# AT32M412_EVB_V0_4.net
KiCad netlist of a schematic drawn in EasyEDA Pro
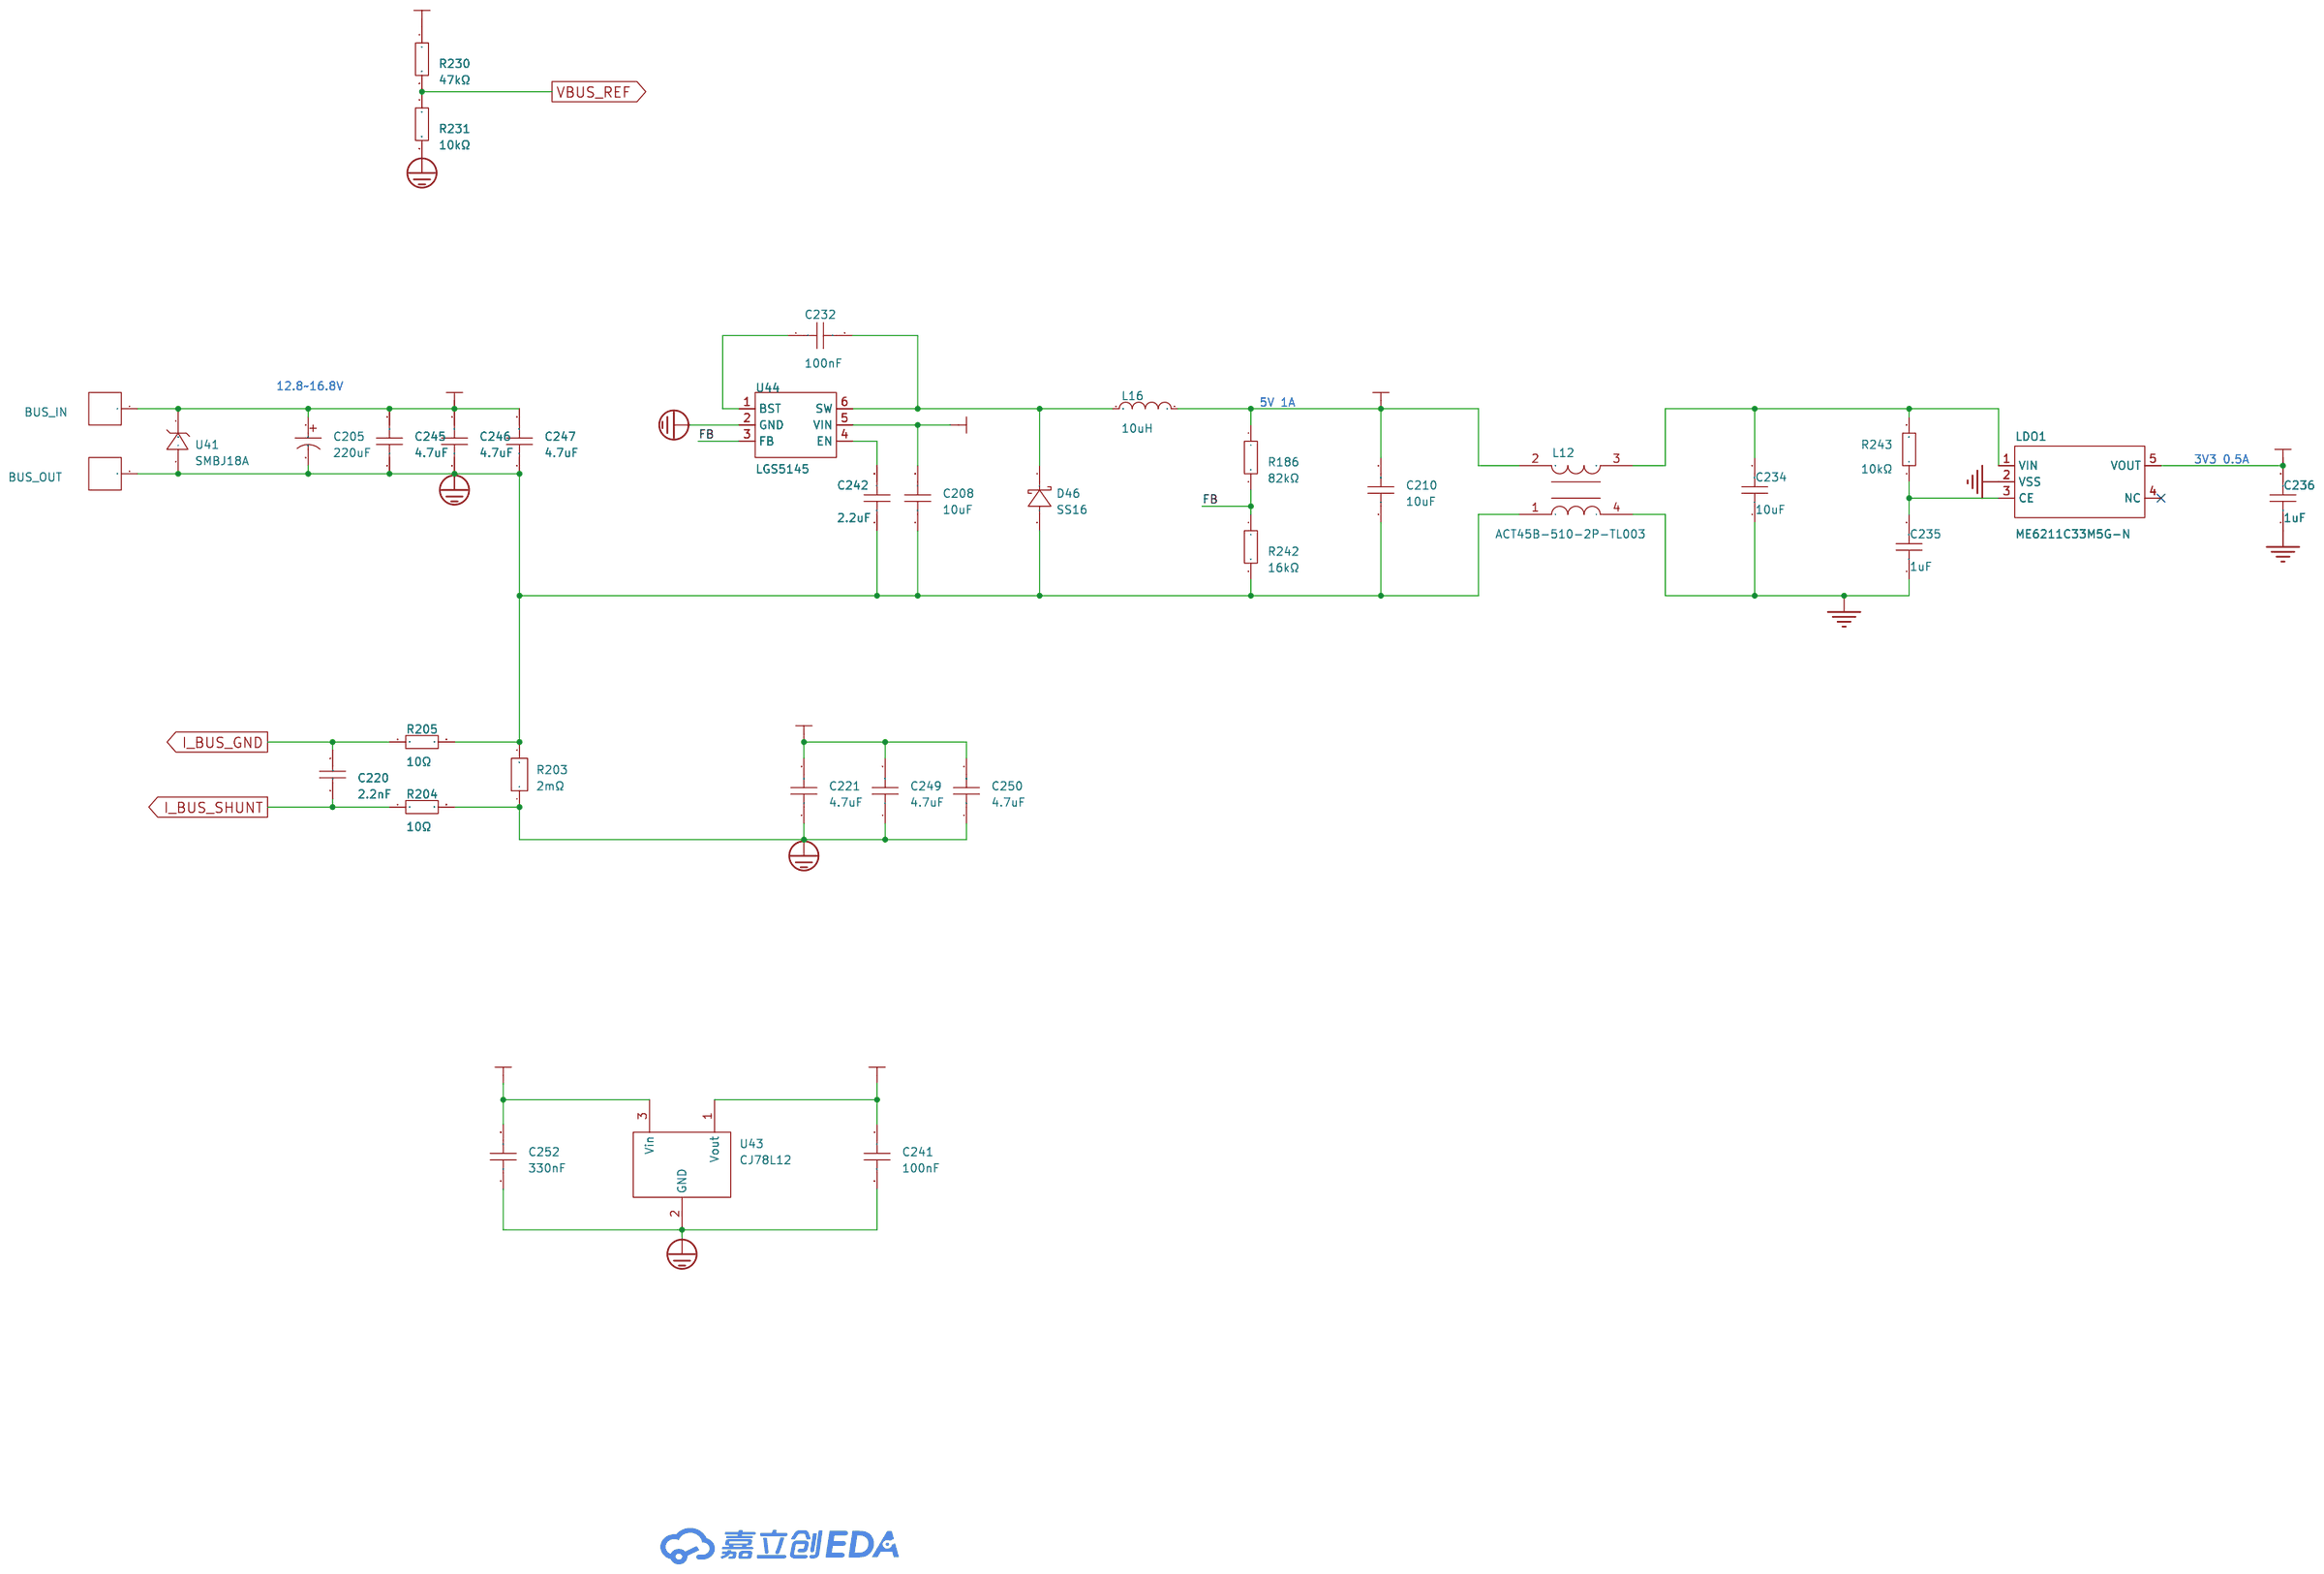
[diagram p0: PWR]
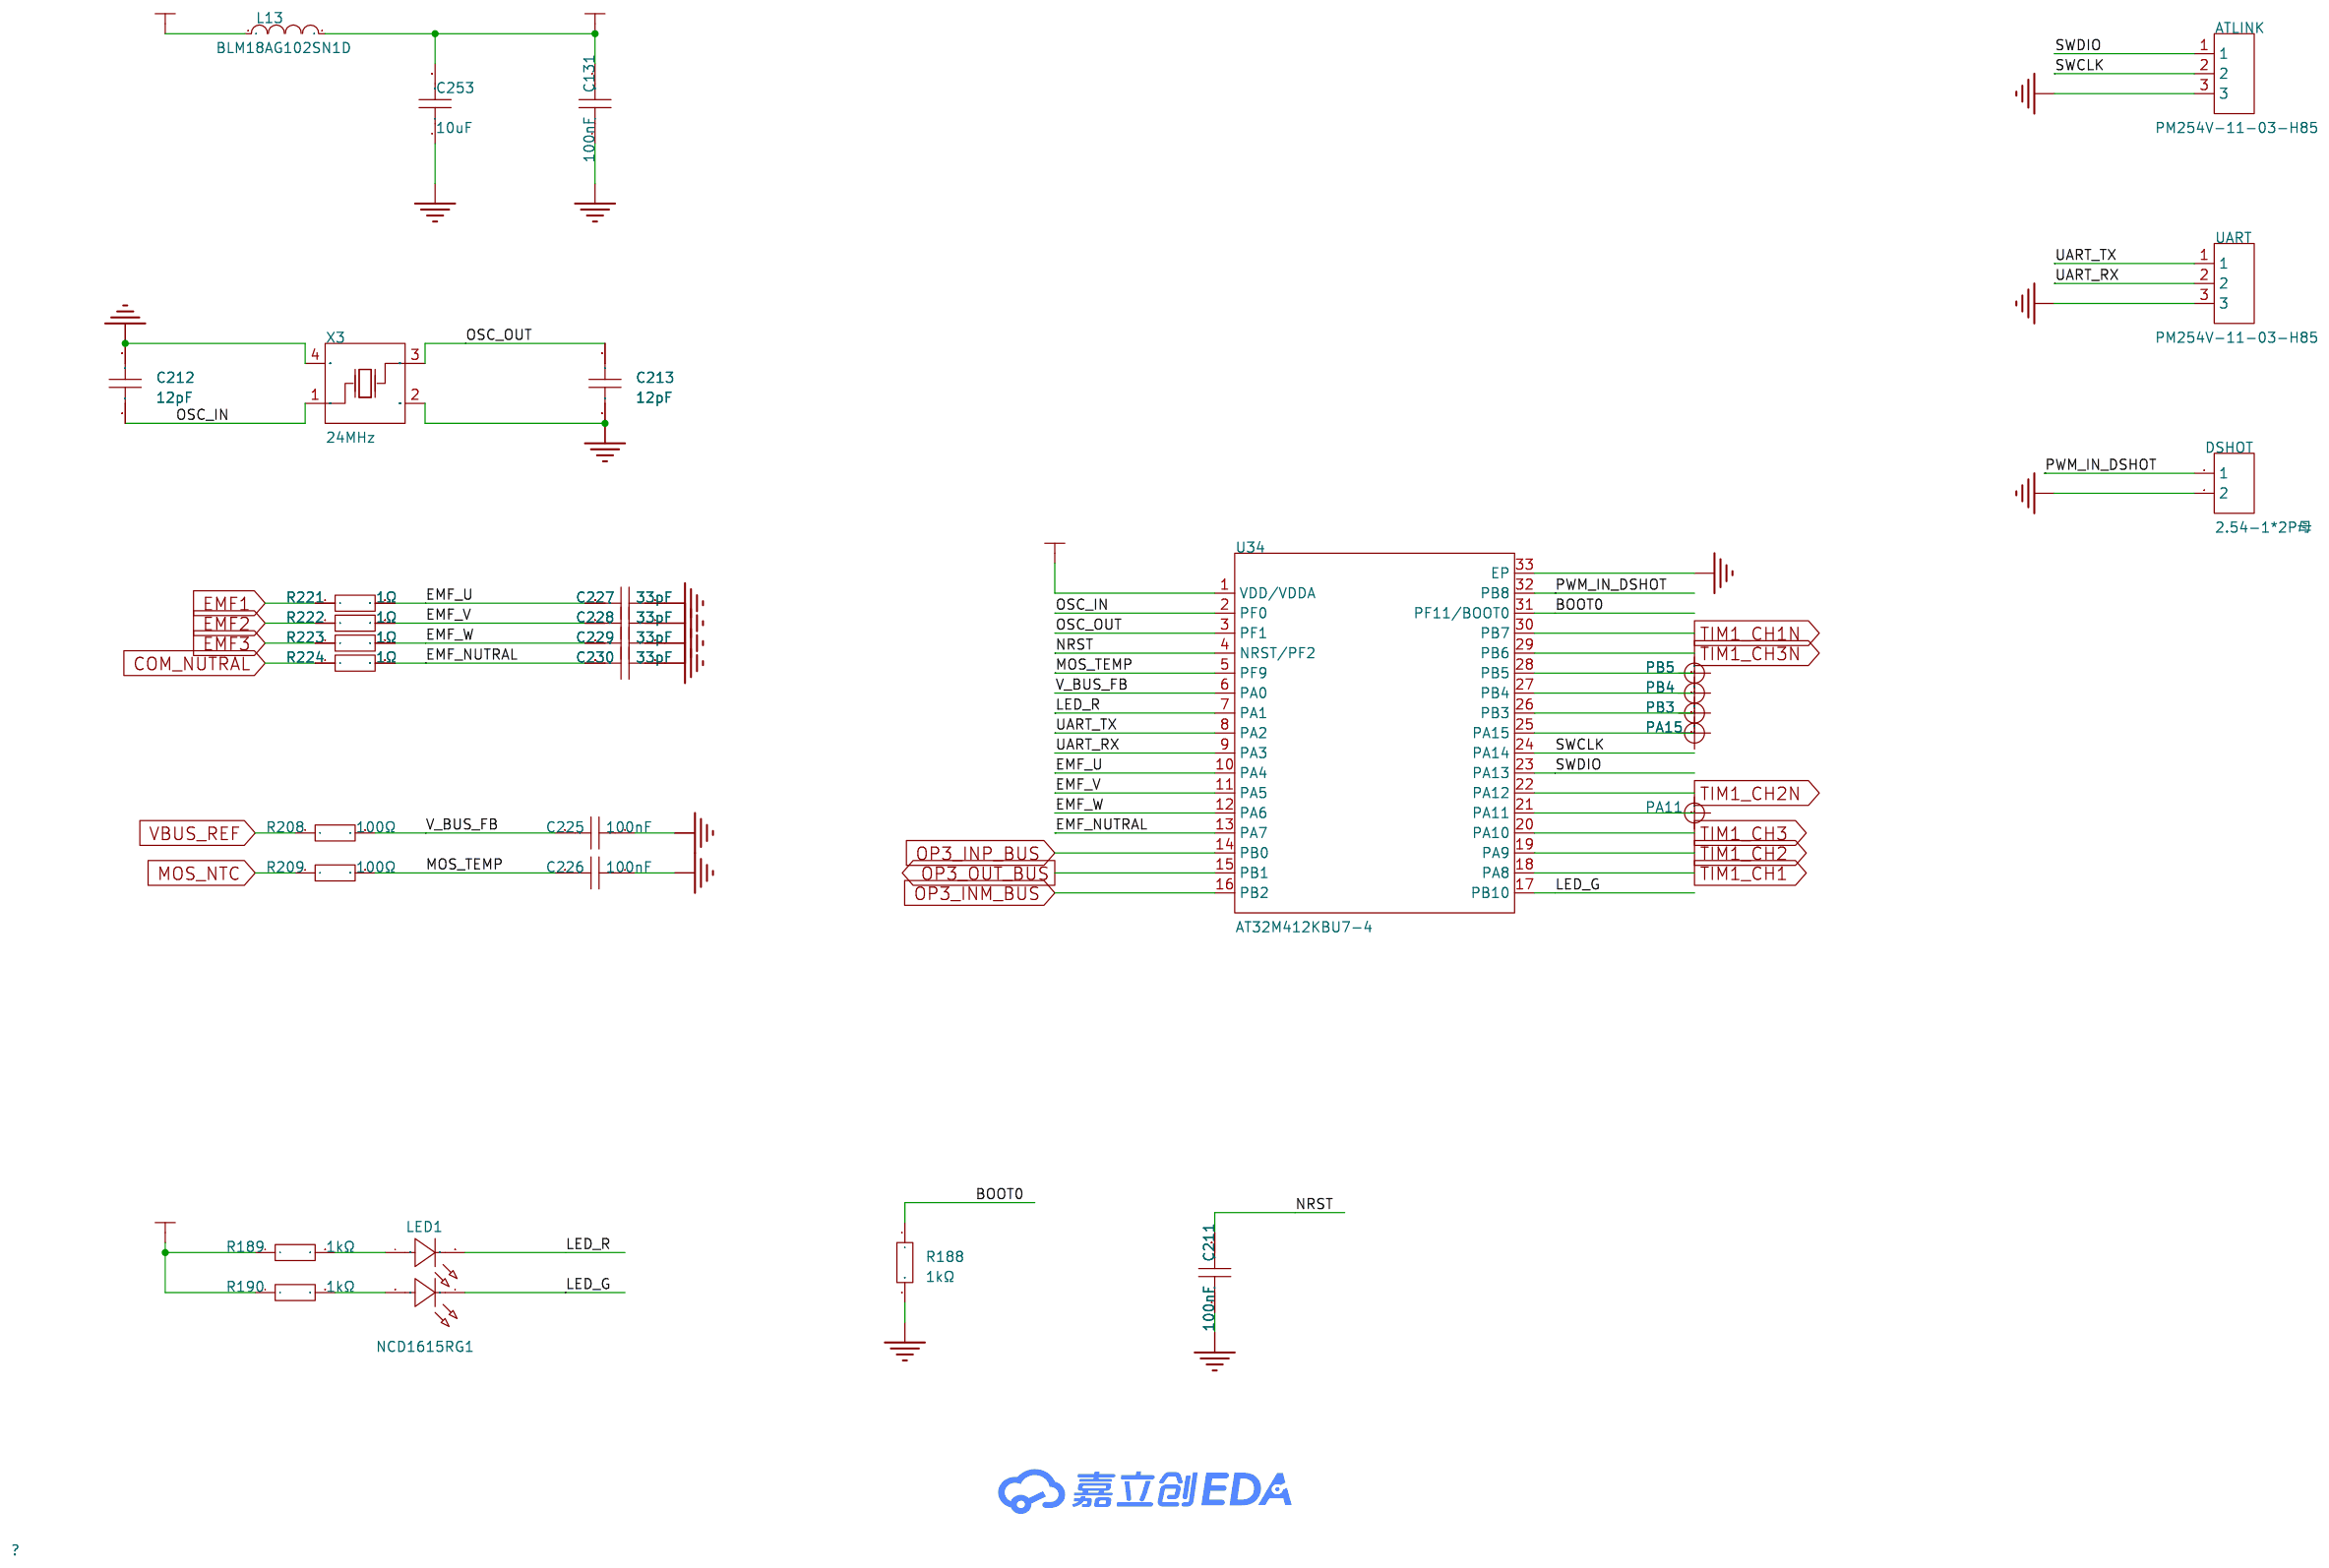
[diagram p1: MCU]
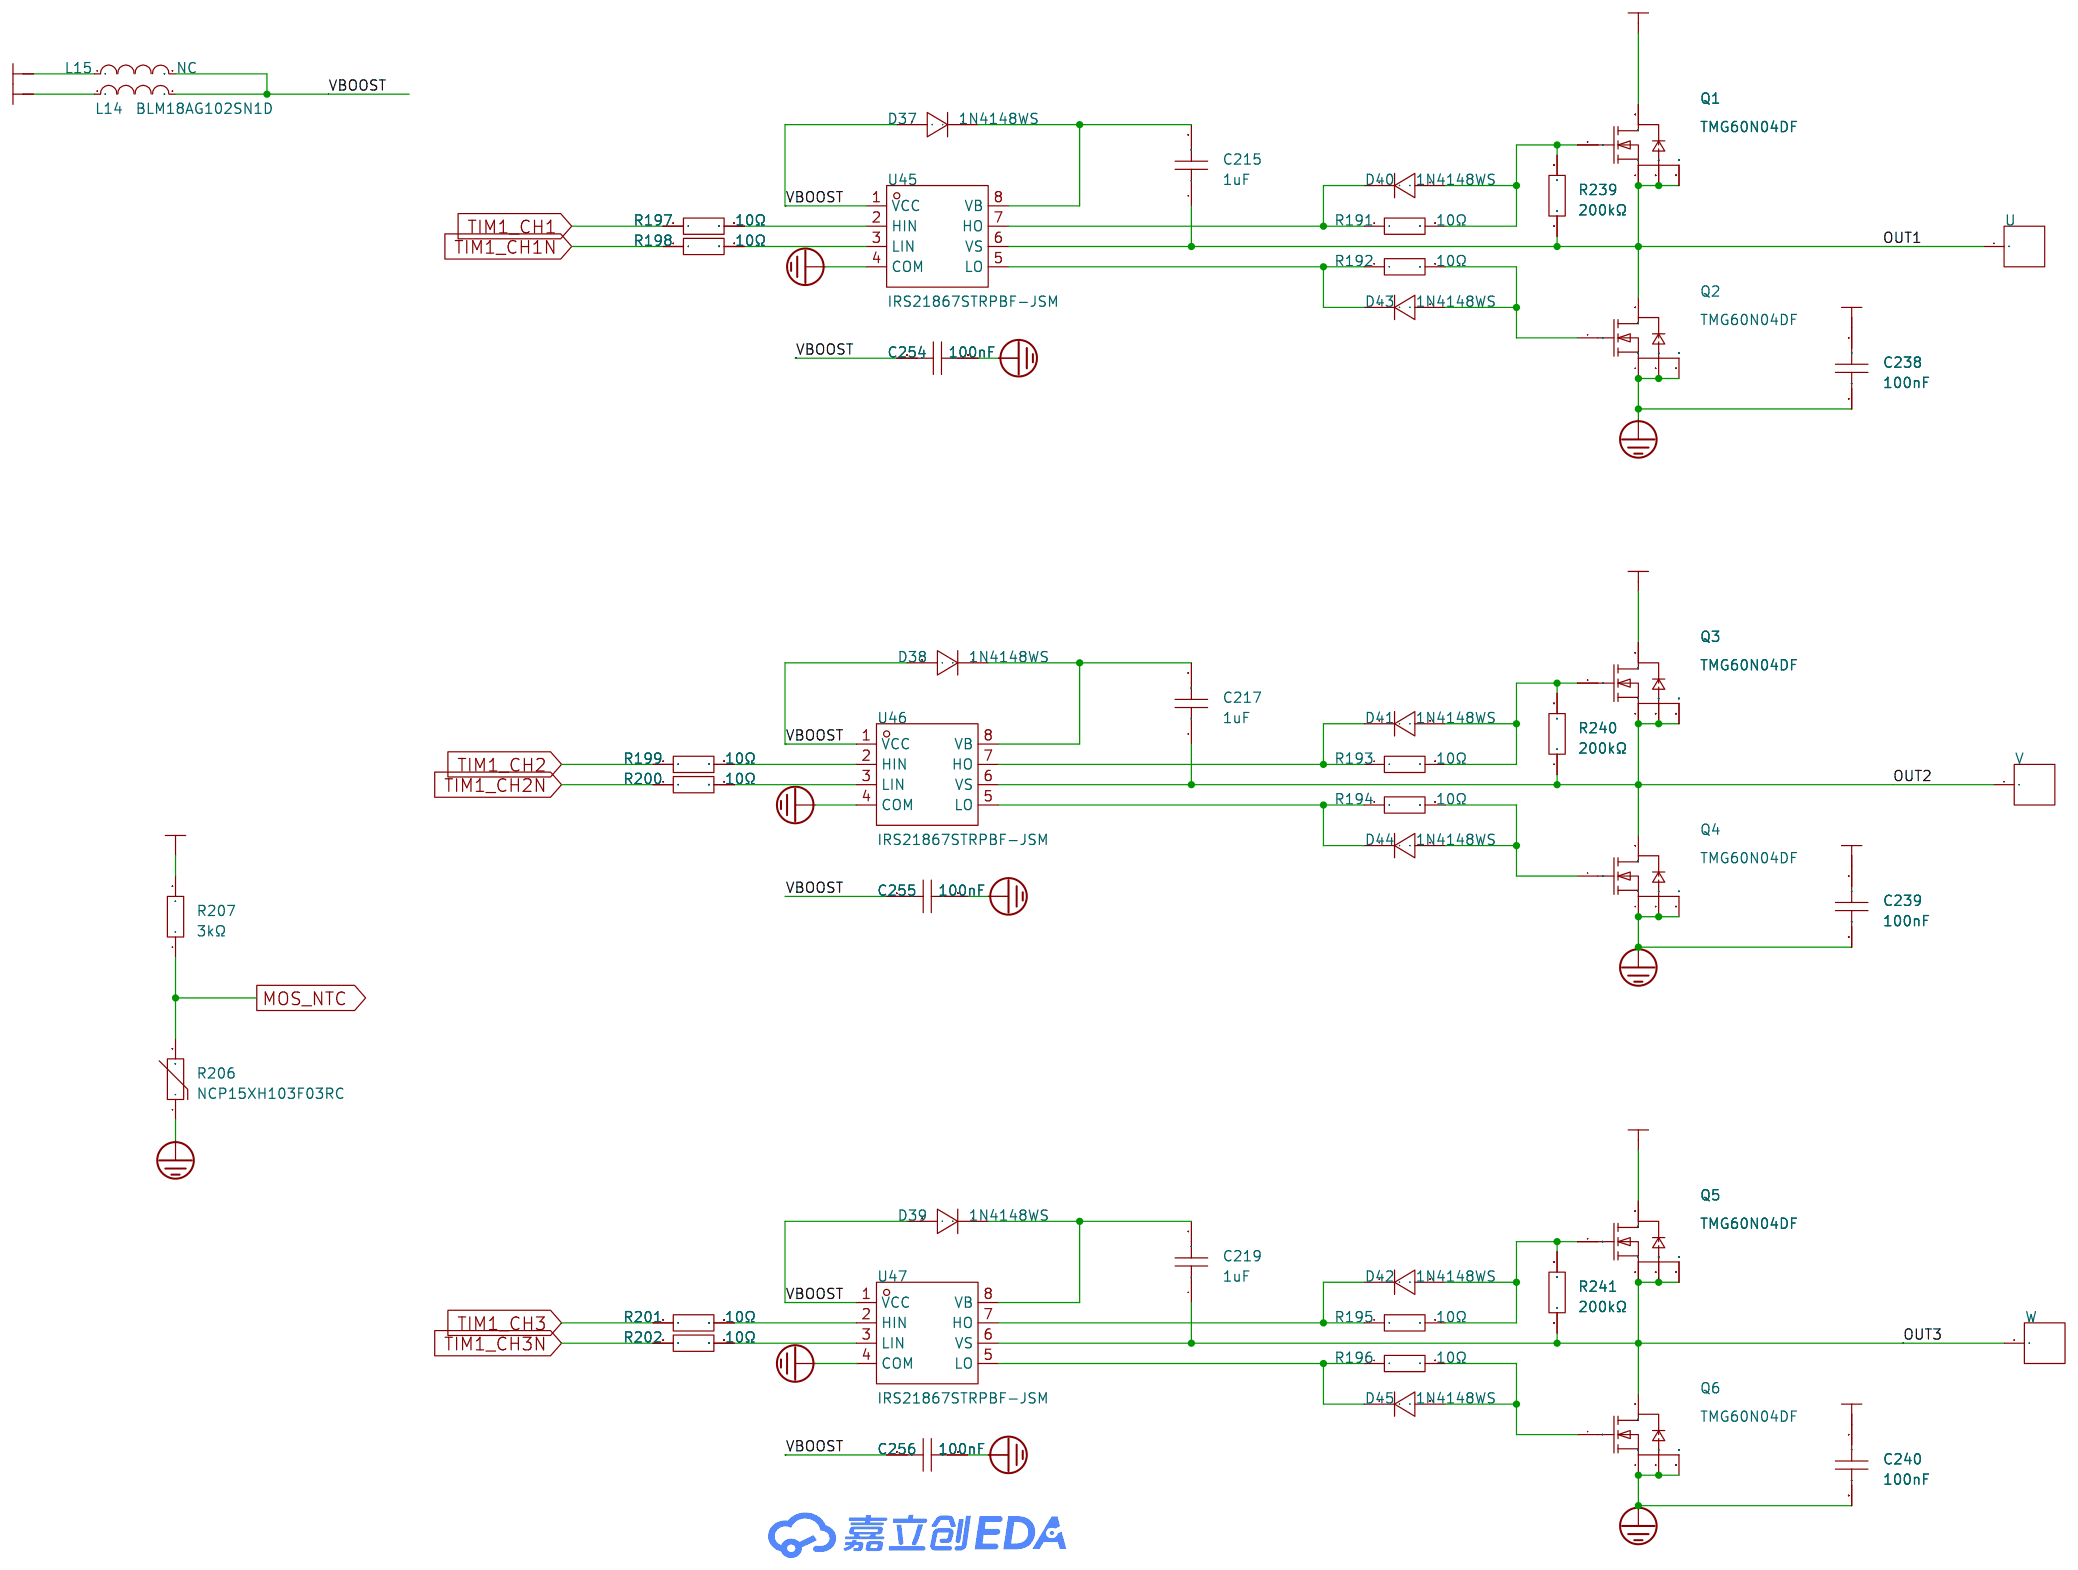
[diagram p2: Driver]
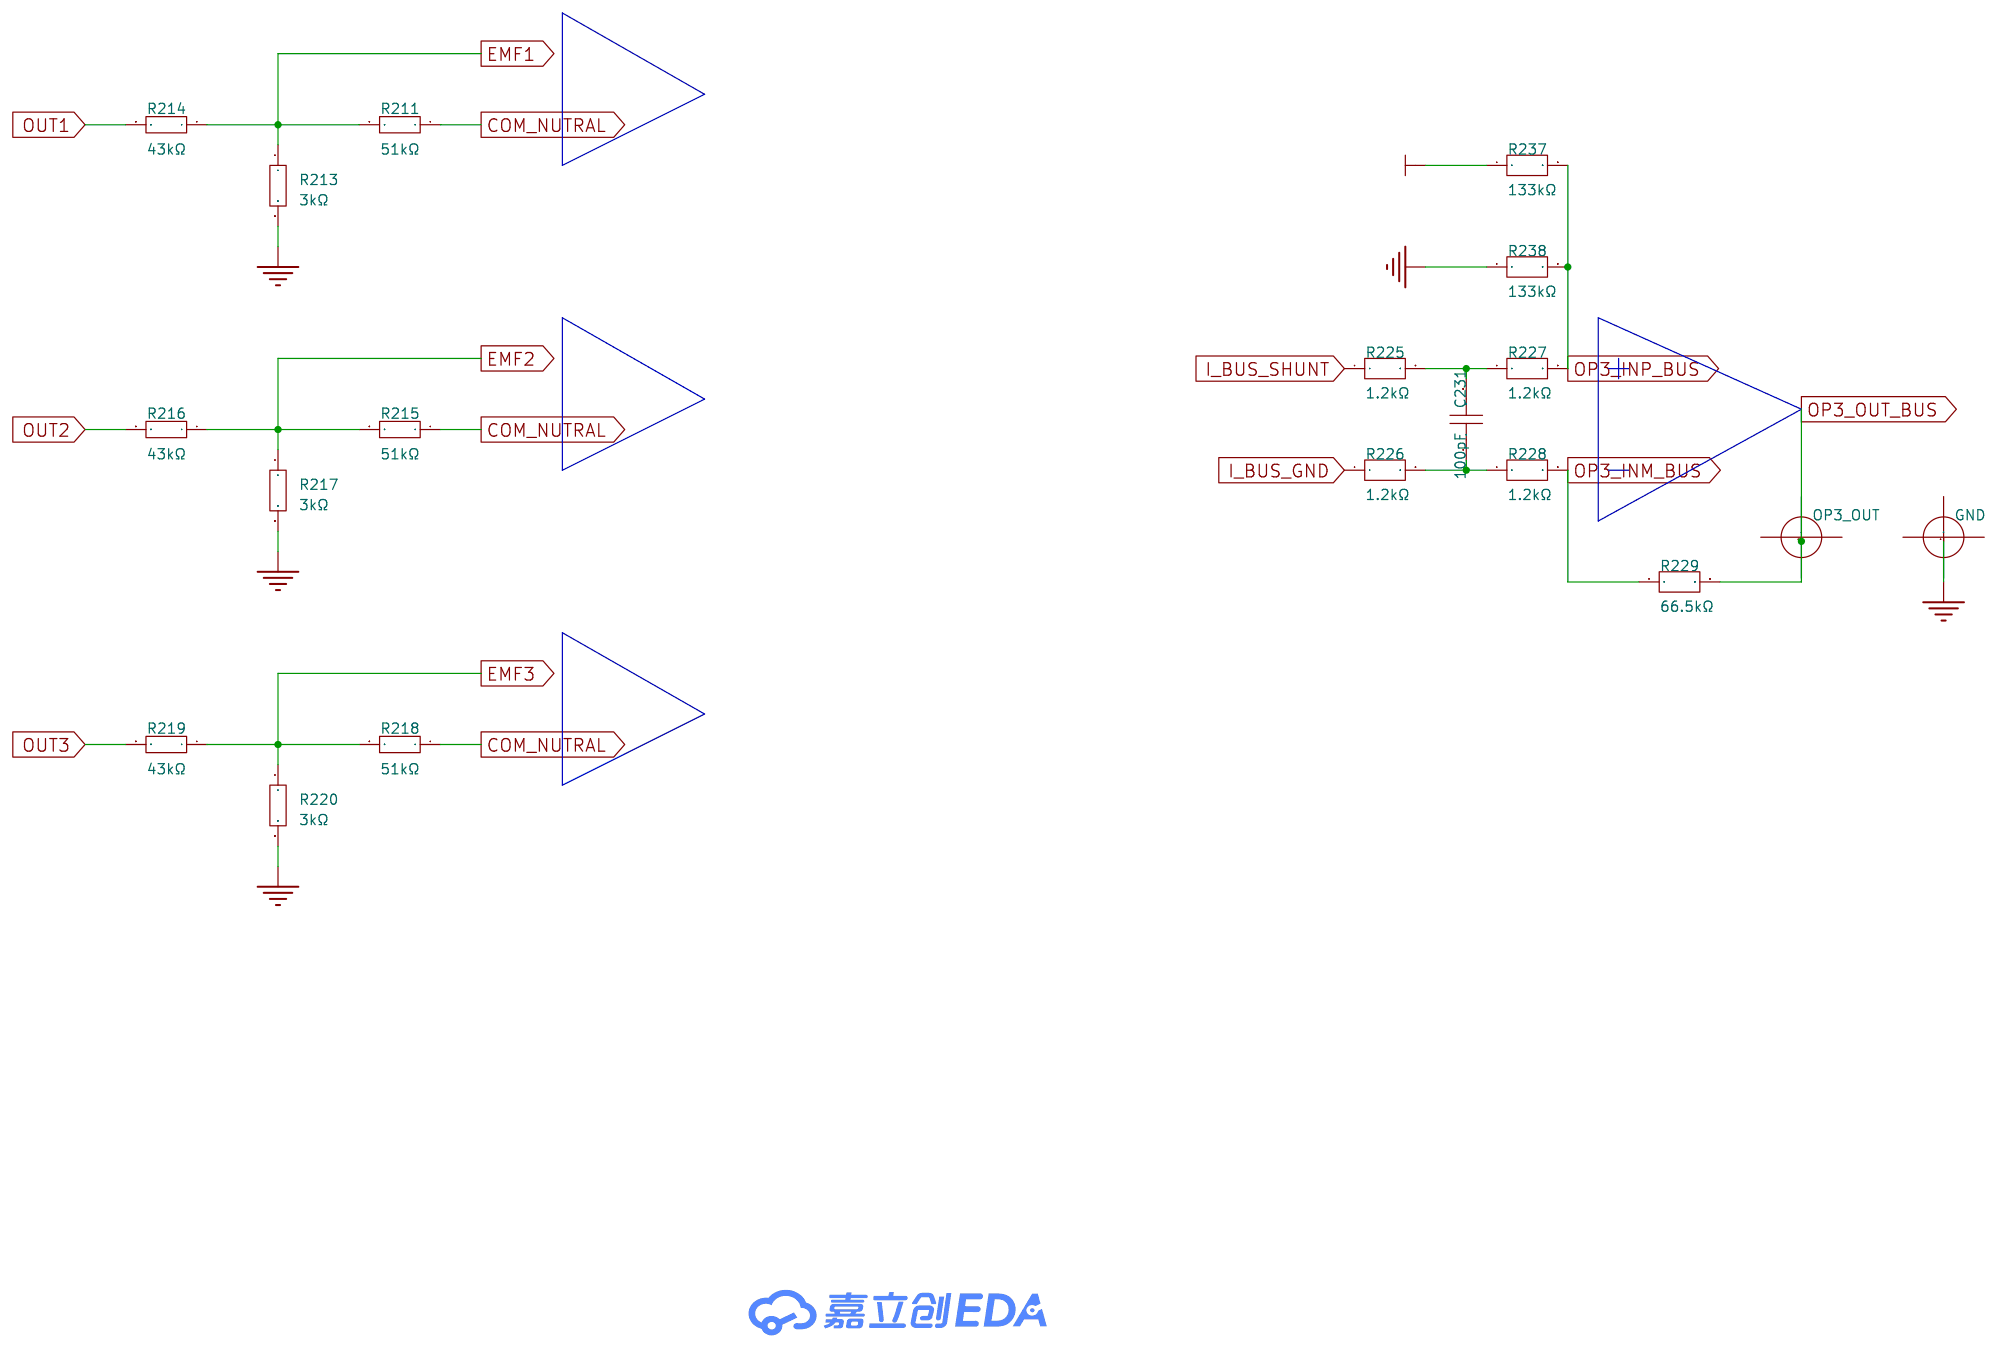
[diagram p3: Sensing]

(export (version "E")
  (design (tool "Eeschema 10.0.6"))
  (components
    (comp (ref "BUS_IN")
      (value "~")
      (footprint "easyedapro:PAD_35A")
      (description "焊盘")
      (libsource (lib "easyedapro") (part "PAD_35A"))
    )
    (comp (ref "BUS_OUT")
      (value "~")
      (footprint "easyedapro:PAD_35A")
      (description "焊盘")
      (libsource (lib "easyedapro") (part "PAD_35A"))
    )
    (comp (ref "C205")
      (value "220uF")
      (footprint "easyedapro:CAP-TH_BD8.0-P3.50-D0.6-FD")
      (description "容值:220uF;精度:±20%;额定电压:35V;")
      (fields (field (name "Manufacturer Part") "ERS1VM221F12OT") (field (name "Manufacturer") "AISHI(艾华集团)"))
      (libsource (lib "easyedapro") (part "ERS1VM221F12OT"))
    )
    (comp (ref "C208")
      (value "10uF")
      (footprint "easyedapro:C0805")
      (description "容值:10uF;精度:±10%;额定电压:25V;温度系数:X5R;")
      (fields
        (field (name "Manufacturer Part") "CL21A106KAYNNNE")
        (field (name "Manufacturer") "SAMSUNG(三星)")
      )
      (libsource (lib "easyedapro") (part "CL21A106KAYNNNE"))
    )
    (comp (ref "C210")
      (value "10uF")
      (footprint "easyedapro:C0402")
      (description "容值:10uF;精度:±20%;额定电压:6.3V;温度系数:X5R;")
      (fields
        (field (name "Manufacturer Part") "CL05A106MQ5NUNC")
        (field (name "Manufacturer") "SAMSUNG(三星)")
      )
      (libsource (lib "easyedapro") (part "GRM155R60J226ME11D"))
    )
    (comp (ref "C220")
      (value "2.2nF")
      (footprint "easyedapro:C0402")
      (description "容值:2.2nF;精度:±10%;额定电压:50V;温度系数:X7R;")
      (fields (field (name "Manufacturer Part") "0402B222K500NT") (field (name "Manufacturer") "FH(风华)"))
      (libsource (lib "easyedapro") (part "0402B222K500NT"))
    )
    (comp (ref "C221")
      (value "4.7uF")
      (footprint "easyedapro:C1210")
      (description "容值:4.7uF;精度:±10%;额定电压:100V;温度系数:X7R;")
      (fields (field (name "Manufacturer Part") "FS32X475K101EGG") (field (name "Manufacturer") "PSA(信昌电陶)"))
      (libsource (lib "easyedapro") (part "FS32X475K101EGG"))
    )
    (comp (ref "C232")
      (value "100nF")
      (footprint "easyedapro:C0402")
      (description "容值:100nF;精度:±10%;额定电压:16V;材质(温度系数):X7R;")
      (fields
        (field (name "Manufacturer Part") "CL05B104KO5NNNC")
        (field (name "Manufacturer") "SAMSUNG(三星)")
      )
      (libsource (lib "easyedapro") (part "CL05B104KO5NNNC"))
    )
    (comp (ref "C234")
      (value "10uF")
      (footprint "easyedapro:C0402")
      (description "容值:10uF;精度:±20%;额定电压:6.3V;温度系数:X5R;")
      (fields
        (field (name "Manufacturer Part") "CL05A106MQ5NUNC")
        (field (name "Manufacturer") "SAMSUNG(三星)")
      )
      (libsource (lib "easyedapro") (part "GRM155R60J226ME11D"))
    )
    (comp (ref "C235")
      (value "1uF")
      (footprint "easyedapro:C0402")
      (description "容值:1uF;精度:±10%;额定电压:25V;温度系数:X5R;")
      (fields
        (field (name "Manufacturer Part") "CL05A105KA5NQNC")
        (field (name "Manufacturer") "SAMSUNG(三星)")
      )
      (libsource (lib "easyedapro") (part "GRM155R60J226ME11D"))
    )
    (comp (ref "C236")
      (value "1uF")
      (footprint "easyedapro:C0402")
      (description "容值:1uF;精度:±10%;额定电压:25V;温度系数:X5R;")
      (fields
        (field (name "Manufacturer Part") "CL05A105KA5NQNC")
        (field (name "Manufacturer") "SAMSUNG(三星)")
      )
      (libsource (lib "easyedapro") (part "GRM155R60J226ME11D"))
    )
    (comp (ref "C241")
      (value "100nF")
      (footprint "easyedapro:C0402")
      (fields
        (field (name "Manufacturer Part") "CL05B104KO5NNNC")
        (field (name "Manufacturer") "SAMSUNG(三星)")
      )
      (libsource (lib "easyedapro") (part "CapAcitance"))
    )
    (comp (ref "C242")
      (value "2.2uF")
      (footprint "easyedapro:C0603")
      (description "容值:2.2uF;精度:±10%;额定电压:50V;温度系数:X5R;")
      (fields
        (field (name "Manufacturer Part") "CL10A225KB8NNNC")
        (field (name "Manufacturer") "SAMSUNG(三星)")
      )
      (libsource (lib "easyedapro") (part "CL10A225KB8NNNC"))
    )
    (comp (ref "C245")
      (value "4.7uF")
      (footprint "easyedapro:C1210")
      (description "容值:4.7uF;精度:±10%;额定电压:100V;温度系数:X7R;")
      (fields (field (name "Manufacturer Part") "FS32X475K101EGG") (field (name "Manufacturer") "PSA(信昌电陶)"))
      (libsource (lib "easyedapro") (part "FS32X475K101EGG"))
    )
    (comp (ref "C246")
      (value "4.7uF")
      (footprint "easyedapro:C1210")
      (description "容值:4.7uF;精度:±10%;额定电压:100V;温度系数:X7R;")
      (fields (field (name "Manufacturer Part") "FS32X475K101EGG") (field (name "Manufacturer") "PSA(信昌电陶)"))
      (libsource (lib "easyedapro") (part "FS32X475K101EGG"))
    )
    (comp (ref "C247")
      (value "4.7uF")
      (footprint "easyedapro:C1210")
      (description "容值:4.7uF;精度:±10%;额定电压:100V;温度系数:X7R;")
      (fields (field (name "Manufacturer Part") "FS32X475K101EGG") (field (name "Manufacturer") "PSA(信昌电陶)"))
      (libsource (lib "easyedapro") (part "FS32X475K101EGG"))
    )
    (comp (ref "C249")
      (value "4.7uF")
      (footprint "easyedapro:C1210")
      (description "容值:4.7uF;精度:±10%;额定电压:100V;温度系数:X7R;")
      (fields (field (name "Manufacturer Part") "FS32X475K101EGG") (field (name "Manufacturer") "PSA(信昌电陶)"))
      (libsource (lib "easyedapro") (part "FS32X475K101EGG"))
    )
    (comp (ref "C250")
      (value "4.7uF")
      (footprint "easyedapro:C1210")
      (description "容值:4.7uF;精度:±10%;额定电压:100V;温度系数:X7R;")
      (fields (field (name "Manufacturer Part") "FS32X475K101EGG") (field (name "Manufacturer") "PSA(信昌电陶)"))
      (libsource (lib "easyedapro") (part "FS32X475K101EGG"))
    )
    (comp (ref "C252")
      (value "330nF")
      (footprint "easyedapro:C0805")
      (description "容值:330nF;精度:±10%;额定电压:100V;温度系数:X7R;")
      (fields
        (field (name "Manufacturer Part") "CC0805KKX7R0BB334")
        (field (name "Manufacturer") "YAGEO(国巨)")
      )
      (libsource (lib "easyedapro") (part "CC0805KKX7R0BB334"))
    )
    (comp (ref "D46")
      (value "SS16")
      (footprint "easyedapro:SMA_L4.3-W2.6-LS5.0-RD")
      (description "二极管配置:独立式;正向压降(Vf):700mV@1A;直流反向耐压(Vr):60V;整流电流:1A;")
      (fields (field (name "Manufacturer") "R+O(宏嘉诚)"))
      (libsource (lib "easyedapro") (part "SS16_C18199176"))
    )
    (comp (ref "L12")
      (value "ACT45B-510-2P-TL003")
      (footprint "easyedapro:IND-SMD_4P-L4.5-W3.2-TL")
      (description "线路数:2;电感 @ 频率:51uH@100kHz;阻抗 @ 频率:2.8kΩ@10MHz;直流电阻(DCR):1Ω;")
      (fields (field (name "Manufacturer") "TDK"))
      (libsource (lib "easyedapro") (part "ACT45B-510-2P-TL003"))
    )
    (comp (ref "L16")
      (value "10uH")
      (footprint "easyedapro:IND-SMD_L2.5-W2.0")
      (description "电感值:10uH;精度:±20%;额定电流:1.2A;饱和电流(Isat):1.6A;类型:一体成型电感;")
      (fields
        (field (name "Manufacturer Part") "FTC252012S100MBCA")
        (field (name "Manufacturer") "cjiang(长江微电)")
      )
      (libsource (lib "easyedapro") (part "FTC252012S100MBCA"))
    )
    (comp (ref "LDO1")
      (value "ME6211C33M5G-N")
      (footprint "easyedapro:SOT-23-5_L3.0-W1.7-P0.95-LS2.8-BL")
      (description "输出类型:固定;工作电压:6V;输出电压:3.3V;输出电流:500mA;电源纹波抑制比(PSRR):70dB@(1kHz)；62dB@(10kHz);输出极性:正极;")
      (fields (field (name "Manufacturer") "MICRONE(南京微盟)"))
      (libsource (lib "easyedapro") (part "ME6211C33M5G-N"))
    )
    (comp (ref "R186")
      (value "82kΩ")
      (footprint "easyedapro:R0402")
      (fields (field (name "Manufacturer Part") "FRC0402F8202TS") (field (name "Manufacturer") "FOJAN(富捷)"))
      (libsource (lib "easyedapro") (part "电阻"))
    )
    (comp (ref "R203")
      (value "2mΩ")
      (footprint "easyedapro:RES-SMD_L6.4-W3.2-1")
      (description "电阻类型:采样电阻;阻值:2mΩ;精度:±1%;额定压降:-;功率:3W;温度系数:±50ppm/°C;安装方式:贴片;")
      (fields
        (field (name "Manufacturer Part") "HoLLR2512-3W-2mR-1%")
        (field (name "Manufacturer") "Milliohm(毫欧)")
      )
      (libsource (lib "easyedapro") (part "HOLLR2512-3W-2MR-1%"))
    )
    (comp (ref "R204")
      (value "10Ω")
      (footprint "easyedapro:R0402")
      (description "电阻类型:厚膜电阻;阻值:10Ω;精度:±1%;功率:62.5mW;工作电压:50V;温度系数:±200ppm/℃;")
      (fields
        (field (name "Manufacturer Part") "0402WGF100JTCE")
        (field (name "Manufacturer") "UNI-ROYAL(厚声)")
      )
      (libsource (lib "easyedapro") (part "电阻"))
    )
    (comp (ref "R205")
      (value "10Ω")
      (footprint "easyedapro:R0402")
      (description "电阻类型:厚膜电阻;阻值:10Ω;精度:±1%;功率:62.5mW;工作电压:50V;温度系数:±200ppm/℃;")
      (fields
        (field (name "Manufacturer Part") "0402WGF100JTCE")
        (field (name "Manufacturer") "UNI-ROYAL(厚声)")
      )
      (libsource (lib "easyedapro") (part "电阻"))
    )
    (comp (ref "R230")
      (value "47kΩ")
      (footprint "easyedapro:R0402")
      (fields
        (field (name "Manufacturer Part") "0402WGF4702TCE")
        (field (name "Manufacturer") "UNI-ROYAL(厚声)")
      )
      (libsource (lib "easyedapro") (part "电阻"))
    )
    (comp (ref "R231")
      (value "10kΩ")
      (footprint "easyedapro:R0402")
      (description "电阻类型:厚膜电阻;阻值:10kΩ;精度:±1%;功率:62.5mW;工作电压:50V;温度系数:±100ppm/℃;")
      (fields
        (field (name "Manufacturer Part") "0402WGF1002TCE")
        (field (name "Manufacturer") "UNI-ROYAL(厚声)")
      )
      (libsource (lib "easyedapro") (part "电阻"))
    )
    (comp (ref "R242")
      (value "16kΩ")
      (footprint "easyedapro:R0402")
      (fields
        (field (name "Manufacturer Part") "0402WGF1602TCE")
        (field (name "Manufacturer") "UNI-ROYAL(厚声)")
      )
      (libsource (lib "easyedapro") (part "电阻"))
    )
    (comp (ref "R243")
      (value "10kΩ")
      (footprint "easyedapro:R0402")
      (description "电阻类型:厚膜电阻;阻值:10kΩ;精度:±1%;功率:62.5mW;工作电压:50V;温度系数:±100ppm/℃;")
      (fields
        (field (name "Manufacturer Part") "0402WGF1002TCE")
        (field (name "Manufacturer") "UNI-ROYAL(厚声)")
      )
      (libsource (lib "easyedapro") (part "电阻"))
    )
    (comp (ref "U41")
      (value "SMBJ18A")
      (footprint "easyedapro:SMB_L4.5-W3.6-LS5.4-RD")
      (fields (field (name "Manufacturer") "R+O(宏嘉诚)"))
      (libsource (lib "easyedapro") (part "SMBJ18A_C19077573"))
    )
    (comp (ref "U43")
      (value "CJ78L12")
      (footprint "easyedapro:SOT-89-3_L4.5-W2.5-P1.50-LS4.2-BR")
      (description "输出类型:固定;工作电压:35V;输出电压:12V;输出电流:100mA;电源纹波抑制比(PSRR):42dB@(120Hz);输出极性:正极;")
      (fields (field (name "Manufacturer") "CJ(江苏长电/长晶)"))
      (libsource (lib "easyedapro") (part "CJ78L12_C8615"))
    )
    (comp (ref "U44")
      (value "LGS5145")
      (footprint "easyedapro:SOT-23-6_L2.9-W1.7-P0.95-LS2.8-BL")
      (description "功能类型:降压型;输出类型:可调;工作电压:4.5V~55V;输出电压:-;输出电流:1A;")
      (fields (field (name "Manufacturer") "Legend-Si(棱晶半导体)"))
      (libsource (lib "easyedapro") (part "LGS5145"))
    )
    (comp (ref "ATLINK")
      (value "PM254V-11-03-H85")
      (footprint "easyedapro:HDR-TH_3P-P2.54-V-F")
      (fields (field (name "Manufacturer") "XFCN(兴飞)"))
      (libsource (lib "easyedapro") (part "PM254V-11-03-H85"))
    )
    (comp (ref "C131")
      (value "100nF")
      (footprint "easyedapro:C0402")
      (fields
        (field (name "Manufacturer Part") "CL05B104KO5NNNC")
        (field (name "Manufacturer") "SAMSUNG(三星)")
      )
      (libsource (lib "easyedapro") (part "CapAcitance"))
    )
    (comp (ref "C211")
      (value "100nF")
      (footprint "easyedapro:C0402")
      (fields
        (field (name "Manufacturer Part") "CL05B104KO5NNNC")
        (field (name "Manufacturer") "SAMSUNG(三星)")
      )
      (libsource (lib "easyedapro") (part "CapAcitance"))
    )
    (comp (ref "C212")
      (value "12pF")
      (footprint "easyedapro:C0402")
      (fields (field (name "Manufacturer Part") "0402CG120J500NT") (field (name "Manufacturer") "FH(风华)"))
      (libsource (lib "easyedapro") (part "CapAcitance"))
    )
    (comp (ref "C213")
      (value "12pF")
      (footprint "easyedapro:C0402")
      (fields (field (name "Manufacturer Part") "0402CG120J500NT") (field (name "Manufacturer") "FH(风华)"))
      (libsource (lib "easyedapro") (part "CapAcitance"))
    )
    (comp (ref "C225")
      (value "100nF")
      (footprint "easyedapro:C0402")
      (fields
        (field (name "Manufacturer Part") "CL05B104KO5NNNC")
        (field (name "Manufacturer") "SAMSUNG(三星)")
      )
      (libsource (lib "easyedapro") (part "CapAcitance"))
    )
    (comp (ref "C226")
      (value "100nF")
      (footprint "easyedapro:C0402")
      (fields
        (field (name "Manufacturer Part") "CL05B104KO5NNNC")
        (field (name "Manufacturer") "SAMSUNG(三星)")
      )
      (libsource (lib "easyedapro") (part "CapAcitance"))
    )
    (comp (ref "C227")
      (value "33pF")
      (footprint "easyedapro:C0402")
      (fields (field (name "Manufacturer Part") "0402CG330J500NT") (field (name "Manufacturer") "FH(风华)"))
      (libsource (lib "easyedapro") (part "CapAcitance"))
    )
    (comp (ref "C228")
      (value "33pF")
      (footprint "easyedapro:C0402")
      (fields (field (name "Manufacturer Part") "0402CG330J500NT") (field (name "Manufacturer") "FH(风华)"))
      (libsource (lib "easyedapro") (part "CapAcitance"))
    )
    (comp (ref "C229")
      (value "33pF")
      (footprint "easyedapro:C0402")
      (fields (field (name "Manufacturer Part") "0402CG330J500NT") (field (name "Manufacturer") "FH(风华)"))
      (libsource (lib "easyedapro") (part "CapAcitance"))
    )
    (comp (ref "C230")
      (value "33pF")
      (footprint "easyedapro:C0402")
      (fields (field (name "Manufacturer Part") "0402CG330J500NT") (field (name "Manufacturer") "FH(风华)"))
      (libsource (lib "easyedapro") (part "CapAcitance"))
    )
    (comp (ref "C253")
      (value "10uF")
      (footprint "easyedapro:C0402")
      (description "容值:10uF;精度:±20%;额定电压:6.3V;温度系数:X5R;")
      (fields
        (field (name "Manufacturer Part") "CL05A106MQ5NUNC")
        (field (name "Manufacturer") "SAMSUNG(三星)")
      )
      (libsource (lib "easyedapro") (part "GRM155R60J226ME11D"))
    )
    (comp (ref "DSHOT")
      (value "2.54-1*2P母")
      (footprint "easyedapro:HDR-TH_2P-P2.54-V-F")
      (fields (field (name "Manufacturer") "BOOMELE(博穆精密)"))
      (libsource (lib "easyedapro") (part "Header-Female-2.54_1x2"))
    )
    (comp (ref "L13")
      (value "BLM18AG102SN1D")
      (footprint "easyedapro:L0603")
      (description "标称阻抗@测试频率:1kΩ@100MHz;误差:±25%;直流电阻(RDC):500mΩ;")
      (fields (field (name "Manufacturer") "muRata(村田)"))
      (libsource (lib "easyedapro") (part "BLM18AG102SN1D"))
    )
    (comp (ref "LED1")
      (value "NCD1615RG1")
      (footprint "easyedapro:LED-SMD_4P-L1.6-W1.5-TL-1")
      (fields (field (name "Manufacturer") "国星光电"))
      (libsource (lib "easyedapro") (part "NCD1615RG1"))
    )
    (comp (ref "PA11")
      (value "~")
      (footprint "easyedapro:Mark-Point-1mm")
      (description "Mark点")
      (libsource (lib "easyedapro") (part "Mark-Point"))
    )
    (comp (ref "PA15")
      (value "~")
      (footprint "easyedapro:Mark-Point-1mm")
      (description "Mark点")
      (libsource (lib "easyedapro") (part "Mark-Point"))
    )
    (comp (ref "PB3")
      (value "~")
      (footprint "easyedapro:Mark-Point-1mm")
      (description "Mark点")
      (libsource (lib "easyedapro") (part "Mark-Point"))
    )
    (comp (ref "PB4")
      (value "~")
      (footprint "easyedapro:Mark-Point-1mm")
      (description "Mark点")
      (libsource (lib "easyedapro") (part "Mark-Point"))
    )
    (comp (ref "PB5")
      (value "~")
      (footprint "easyedapro:Mark-Point-1mm")
      (description "Mark点")
      (libsource (lib "easyedapro") (part "Mark-Point"))
    )
    (comp (ref "R188")
      (value "1kΩ")
      (footprint "easyedapro:R0402")
      (description "电阻类型:厚膜电阻;阻值:1kΩ;精度:±1%;功率:62.5mW;工作电压:50V;温度系数:±100ppm/℃;")
      (fields
        (field (name "Manufacturer Part") "0402WGF1001TCE")
        (field (name "Manufacturer") "UNI-ROYAL(厚声)")
      )
      (libsource (lib "easyedapro") (part "电阻"))
    )
    (comp (ref "R189")
      (value "1kΩ")
      (footprint "easyedapro:R0402")
      (description "电阻类型:厚膜电阻;阻值:1kΩ;精度:±1%;功率:62.5mW;工作电压:50V;温度系数:±100ppm/℃;")
      (fields
        (field (name "Manufacturer Part") "0402WGF1001TCE")
        (field (name "Manufacturer") "UNI-ROYAL(厚声)")
      )
      (libsource (lib "easyedapro") (part "电阻"))
    )
    (comp (ref "R190")
      (value "1kΩ")
      (footprint "easyedapro:R0402")
      (description "电阻类型:厚膜电阻;阻值:1kΩ;精度:±1%;功率:62.5mW;工作电压:50V;温度系数:±100ppm/℃;")
      (fields
        (field (name "Manufacturer Part") "0402WGF1001TCE")
        (field (name "Manufacturer") "UNI-ROYAL(厚声)")
      )
      (libsource (lib "easyedapro") (part "电阻"))
    )
    (comp (ref "R208")
      (value "100Ω")
      (footprint "easyedapro:R0402")
      (fields
        (field (name "Manufacturer Part") "0402WGF1000TCE")
        (field (name "Manufacturer") "UNI-ROYAL(厚声)")
      )
      (libsource (lib "easyedapro") (part "电阻"))
    )
    (comp (ref "R209")
      (value "100Ω")
      (footprint "easyedapro:R0402")
      (fields
        (field (name "Manufacturer Part") "0402WGF1000TCE")
        (field (name "Manufacturer") "UNI-ROYAL(厚声)")
      )
      (libsource (lib "easyedapro") (part "电阻"))
    )
    (comp (ref "R221")
      (value "1Ω")
      (footprint "easyedapro:R0402")
      (fields
        (field (name "Manufacturer Part") "0402WGF100KTCE")
        (field (name "Manufacturer") "UNI-ROYAL(厚声)")
      )
      (libsource (lib "easyedapro") (part "电阻"))
    )
    (comp (ref "R222")
      (value "1Ω")
      (footprint "easyedapro:R0402")
      (fields
        (field (name "Manufacturer Part") "0402WGF100KTCE")
        (field (name "Manufacturer") "UNI-ROYAL(厚声)")
      )
      (libsource (lib "easyedapro") (part "电阻"))
    )
    (comp (ref "R223")
      (value "1Ω")
      (footprint "easyedapro:R0402")
      (fields
        (field (name "Manufacturer Part") "0402WGF100KTCE")
        (field (name "Manufacturer") "UNI-ROYAL(厚声)")
      )
      (libsource (lib "easyedapro") (part "电阻"))
    )
    (comp (ref "R224")
      (value "1Ω")
      (footprint "easyedapro:R0402")
      (fields
        (field (name "Manufacturer Part") "0402WGF100KTCE")
        (field (name "Manufacturer") "UNI-ROYAL(厚声)")
      )
      (libsource (lib "easyedapro") (part "电阻"))
    )
    (comp (ref "U34")
      (value "AT32M412KBU7-4")
      (footprint "easyedapro:WQFN-32_L4.0-W4.0-P0.40-TL-EP2.7")
      (fields (field (name "Manufacturer") "ARTERY(雅特力)"))
      (libsource (lib "easyedapro") (part "AT32M412KBU7-4"))
    )
    (comp (ref "UART")
      (value "PM254V-11-03-H85")
      (footprint "easyedapro:HDR-TH_3P-P2.54-V-F")
      (fields (field (name "Manufacturer") "XFCN(兴飞)"))
      (libsource (lib "easyedapro") (part "PM254V-11-03-H85"))
    )
    (comp (ref "X3")
      (value "24MHz")
      (footprint "easyedapro:CRYSTAL-SMD_4P-L3.2-W2.5-BL")
      (description "晶振类型:贴片晶振;频率:24MHz;常温频差:±10ppm;负载电容:12pF;频率稳定度:±20ppm;")
      (fields (field (name "Manufacturer Part") "X322524MOB4SI") (field (name "Manufacturer") "YXC(扬兴晶振)"))
      (libsource (lib "easyedapro") (part "X322524MOB4SI"))
    )
    (comp (ref "C215")
      (value "1uF")
      (footprint "easyedapro:C0603")
      (description "容值:1uF;精度:±10%;额定电压:50V;温度系数:X7R;")
      (fields
        (field (name "Manufacturer Part") "CC0603KRX7R9BB105")
        (field (name "Manufacturer") "YAGEO(国巨)")
      )
      (libsource (lib "easyedapro") (part "CC0603KRX7R9BB105"))
    )
    (comp (ref "C217")
      (value "1uF")
      (footprint "easyedapro:C0603")
      (description "容值:1uF;精度:±10%;额定电压:50V;温度系数:X7R;")
      (fields
        (field (name "Manufacturer Part") "CC0603KRX7R9BB105")
        (field (name "Manufacturer") "YAGEO(国巨)")
      )
      (libsource (lib "easyedapro") (part "CC0603KRX7R9BB105"))
    )
    (comp (ref "C219")
      (value "1uF")
      (footprint "easyedapro:C0603")
      (description "容值:1uF;精度:±10%;额定电压:50V;温度系数:X7R;")
      (fields
        (field (name "Manufacturer Part") "CC0603KRX7R9BB105")
        (field (name "Manufacturer") "YAGEO(国巨)")
      )
      (libsource (lib "easyedapro") (part "CC0603KRX7R9BB105"))
    )
    (comp (ref "C238")
      (value "100nF")
      (footprint "easyedapro:C0402")
      (description "容值:100nF;精度:±10%;额定电压:50V;温度系数:X7R;")
      (fields
        (field (name "Manufacturer Part") "CL05B104KB54PNC")
        (field (name "Manufacturer") "SAMSUNG(三星)")
      )
      (libsource (lib "easyedapro") (part "CL05B104KB54PNC"))
    )
    (comp (ref "C239")
      (value "100nF")
      (footprint "easyedapro:C0402")
      (description "容值:100nF;精度:±10%;额定电压:50V;温度系数:X7R;")
      (fields
        (field (name "Manufacturer Part") "CL05B104KB54PNC")
        (field (name "Manufacturer") "SAMSUNG(三星)")
      )
      (libsource (lib "easyedapro") (part "CL05B104KB54PNC"))
    )
    (comp (ref "C240")
      (value "100nF")
      (footprint "easyedapro:C0402")
      (description "容值:100nF;精度:±10%;额定电压:50V;温度系数:X7R;")
      (fields
        (field (name "Manufacturer Part") "CL05B104KB54PNC")
        (field (name "Manufacturer") "SAMSUNG(三星)")
      )
      (libsource (lib "easyedapro") (part "CL05B104KB54PNC"))
    )
    (comp (ref "C254")
      (value "100nF")
      (footprint "easyedapro:C0402")
      (description "容值:100nF;精度:±10%;额定电压:50V;温度系数:X7R;")
      (fields
        (field (name "Manufacturer Part") "CL05B104KB54PNC")
        (field (name "Manufacturer") "SAMSUNG(三星)")
      )
      (libsource (lib "easyedapro") (part "CL05B104KB54PNC"))
    )
    (comp (ref "C255")
      (value "100nF")
      (footprint "easyedapro:C0402")
      (description "容值:100nF;精度:±10%;额定电压:50V;温度系数:X7R;")
      (fields
        (field (name "Manufacturer Part") "CL05B104KB54PNC")
        (field (name "Manufacturer") "SAMSUNG(三星)")
      )
      (libsource (lib "easyedapro") (part "CL05B104KB54PNC"))
    )
    (comp (ref "C256")
      (value "100nF")
      (footprint "easyedapro:C0402")
      (description "容值:100nF;精度:±10%;额定电压:50V;温度系数:X7R;")
      (fields
        (field (name "Manufacturer Part") "CL05B104KB54PNC")
        (field (name "Manufacturer") "SAMSUNG(三星)")
      )
      (libsource (lib "easyedapro") (part "CL05B104KB54PNC"))
    )
    (comp (ref "D37")
      (value "1N4148WS")
      (footprint "easyedapro:SOD-323_L1.8-W1.3-LS2.5-RD")
      (description "二极管配置:独立式;正向压降(Vf):1.25V@150mA;直流反向耐压(Vr):100V;整流电流:150mA;反向恢复时间(Trr):4ns;")
      (fields (field (name "Manufacturer") "CJ(江苏长电/长晶)"))
      (libsource (lib "easyedapro") (part "1N4148WS T4"))
    )
    (comp (ref "D38")
      (value "1N4148WS")
      (footprint "easyedapro:SOD-323_L1.8-W1.3-LS2.5-RD")
      (description "二极管配置:独立式;正向压降(Vf):1.25V@150mA;直流反向耐压(Vr):100V;整流电流:150mA;反向恢复时间(Trr):4ns;")
      (fields (field (name "Manufacturer") "CJ(江苏长电/长晶)"))
      (libsource (lib "easyedapro") (part "1N4148WS T4"))
    )
    (comp (ref "D39")
      (value "1N4148WS")
      (footprint "easyedapro:SOD-323_L1.8-W1.3-LS2.5-RD")
      (description "二极管配置:独立式;正向压降(Vf):1.25V@150mA;直流反向耐压(Vr):100V;整流电流:150mA;反向恢复时间(Trr):4ns;")
      (fields (field (name "Manufacturer") "CJ(江苏长电/长晶)"))
      (libsource (lib "easyedapro") (part "1N4148WS T4"))
    )
    (comp (ref "D40")
      (value "1N4148WS")
      (footprint "easyedapro:SOD-323_L1.8-W1.3-LS2.5-RD")
      (description "二极管配置:独立式;正向压降(Vf):1.25V@150mA;直流反向耐压(Vr):100V;整流电流:150mA;反向恢复时间(Trr):4ns;")
      (fields (field (name "Manufacturer") "CJ(江苏长电/长晶)"))
      (libsource (lib "easyedapro") (part "1N4148WS T4"))
    )
    (comp (ref "D41")
      (value "1N4148WS")
      (footprint "easyedapro:SOD-323_L1.8-W1.3-LS2.5-RD")
      (description "二极管配置:独立式;正向压降(Vf):1.25V@150mA;直流反向耐压(Vr):100V;整流电流:150mA;反向恢复时间(Trr):4ns;")
      (fields (field (name "Manufacturer") "CJ(江苏长电/长晶)"))
      (libsource (lib "easyedapro") (part "1N4148WS T4"))
    )
    (comp (ref "D42")
      (value "1N4148WS")
      (footprint "easyedapro:SOD-323_L1.8-W1.3-LS2.5-RD")
      (description "二极管配置:独立式;正向压降(Vf):1.25V@150mA;直流反向耐压(Vr):100V;整流电流:150mA;反向恢复时间(Trr):4ns;")
      (fields (field (name "Manufacturer") "CJ(江苏长电/长晶)"))
      (libsource (lib "easyedapro") (part "1N4148WS T4"))
    )
    (comp (ref "D43")
      (value "1N4148WS")
      (footprint "easyedapro:SOD-323_L1.8-W1.3-LS2.5-RD")
      (description "二极管配置:独立式;正向压降(Vf):1.25V@150mA;直流反向耐压(Vr):100V;整流电流:150mA;反向恢复时间(Trr):4ns;")
      (fields (field (name "Manufacturer") "CJ(江苏长电/长晶)"))
      (libsource (lib "easyedapro") (part "1N4148WS T4"))
    )
    (comp (ref "D44")
      (value "1N4148WS")
      (footprint "easyedapro:SOD-323_L1.8-W1.3-LS2.5-RD")
      (description "二极管配置:独立式;正向压降(Vf):1.25V@150mA;直流反向耐压(Vr):100V;整流电流:150mA;反向恢复时间(Trr):4ns;")
      (fields (field (name "Manufacturer") "CJ(江苏长电/长晶)"))
      (libsource (lib "easyedapro") (part "1N4148WS T4"))
    )
    (comp (ref "D45")
      (value "1N4148WS")
      (footprint "easyedapro:SOD-323_L1.8-W1.3-LS2.5-RD")
      (description "二极管配置:独立式;正向压降(Vf):1.25V@150mA;直流反向耐压(Vr):100V;整流电流:150mA;反向恢复时间(Trr):4ns;")
      (fields (field (name "Manufacturer") "CJ(江苏长电/长晶)"))
      (libsource (lib "easyedapro") (part "1N4148WS T4"))
    )
    (comp (ref "L14")
      (value "BLM18AG102SN1D")
      (footprint "easyedapro:L0603")
      (description "标称阻抗@测试频率:1kΩ@100MHz;误差:±25%;直流电阻(RDC):500mΩ;")
      (fields (field (name "Manufacturer") "muRata(村田)"))
      (libsource (lib "easyedapro") (part "BLM18AG102SN1D"))
    )
    (comp (ref "L15")
      (value "NC")
      (footprint "easyedapro:L0603")
      (description "标称阻抗@测试频率:1kΩ@100MHz;误差:±25%;直流电阻(RDC):500mΩ;")
      (fields (field (name "Manufacturer") "muRata(村田)"))
      (libsource (lib "easyedapro") (part "BLM18AG102SN1D"))
    )
    (comp (ref "Q1")
      (value "TMG60N04DF")
      (footprint "easyedapro:POWERDI3333-8_DMN7022LFGQ-7")
      (fields (field (name "Manufacturer") "TMC(台懋)"))
      (libsource (lib "easyedapro") (part "TMG60N04DF"))
    )
    (comp (ref "Q2")
      (value "TMG60N04DF")
      (footprint "easyedapro:POWERDI3333-8_DMN7022LFGQ-7")
      (fields (field (name "Manufacturer") "TMC(台懋)"))
      (libsource (lib "easyedapro") (part "TMG60N04DF"))
    )
    (comp (ref "Q3")
      (value "TMG60N04DF")
      (footprint "easyedapro:POWERDI3333-8_DMN7022LFGQ-7")
      (fields (field (name "Manufacturer") "TMC(台懋)"))
      (libsource (lib "easyedapro") (part "TMG60N04DF"))
    )
    (comp (ref "Q4")
      (value "TMG60N04DF")
      (footprint "easyedapro:POWERDI3333-8_DMN7022LFGQ-7")
      (fields (field (name "Manufacturer") "TMC(台懋)"))
      (libsource (lib "easyedapro") (part "TMG60N04DF"))
    )
    (comp (ref "Q5")
      (value "TMG60N04DF")
      (footprint "easyedapro:POWERDI3333-8_DMN7022LFGQ-7")
      (fields (field (name "Manufacturer") "TMC(台懋)"))
      (libsource (lib "easyedapro") (part "TMG60N04DF"))
    )
    (comp (ref "Q6")
      (value "TMG60N04DF")
      (footprint "easyedapro:POWERDI3333-8_DMN7022LFGQ-7")
      (fields (field (name "Manufacturer") "TMC(台懋)"))
      (libsource (lib "easyedapro") (part "TMG60N04DF"))
    )
    (comp (ref "R191")
      (value "10Ω")
      (footprint "easyedapro:R0402")
      (description "电阻类型:厚膜电阻;阻值:10Ω;精度:±1%;功率:62.5mW;工作电压:50V;温度系数:±200ppm/℃;")
      (fields
        (field (name "Manufacturer Part") "0402WGF100JTCE")
        (field (name "Manufacturer") "UNI-ROYAL(厚声)")
      )
      (libsource (lib "easyedapro") (part "电阻"))
    )
    (comp (ref "R192")
      (value "10Ω")
      (footprint "easyedapro:R0402")
      (description "电阻类型:厚膜电阻;阻值:10Ω;精度:±1%;功率:62.5mW;工作电压:50V;温度系数:±200ppm/℃;")
      (fields
        (field (name "Manufacturer Part") "0402WGF100JTCE")
        (field (name "Manufacturer") "UNI-ROYAL(厚声)")
      )
      (libsource (lib "easyedapro") (part "电阻"))
    )
    (comp (ref "R193")
      (value "10Ω")
      (footprint "easyedapro:R0402")
      (description "电阻类型:厚膜电阻;阻值:10Ω;精度:±1%;功率:62.5mW;工作电压:50V;温度系数:±200ppm/℃;")
      (fields
        (field (name "Manufacturer Part") "0402WGF100JTCE")
        (field (name "Manufacturer") "UNI-ROYAL(厚声)")
      )
      (libsource (lib "easyedapro") (part "电阻"))
    )
    (comp (ref "R194")
      (value "10Ω")
      (footprint "easyedapro:R0402")
      (description "电阻类型:厚膜电阻;阻值:10Ω;精度:±1%;功率:62.5mW;工作电压:50V;温度系数:±200ppm/℃;")
      (fields
        (field (name "Manufacturer Part") "0402WGF100JTCE")
        (field (name "Manufacturer") "UNI-ROYAL(厚声)")
      )
      (libsource (lib "easyedapro") (part "电阻"))
    )
    (comp (ref "R195")
      (value "10Ω")
      (footprint "easyedapro:R0402")
      (description "电阻类型:厚膜电阻;阻值:10Ω;精度:±1%;功率:62.5mW;工作电压:50V;温度系数:±200ppm/℃;")
      (fields
        (field (name "Manufacturer Part") "0402WGF100JTCE")
        (field (name "Manufacturer") "UNI-ROYAL(厚声)")
      )
      (libsource (lib "easyedapro") (part "电阻"))
    )
    (comp (ref "R196")
      (value "10Ω")
      (footprint "easyedapro:R0402")
      (description "电阻类型:厚膜电阻;阻值:10Ω;精度:±1%;功率:62.5mW;工作电压:50V;温度系数:±200ppm/℃;")
      (fields
        (field (name "Manufacturer Part") "0402WGF100JTCE")
        (field (name "Manufacturer") "UNI-ROYAL(厚声)")
      )
      (libsource (lib "easyedapro") (part "电阻"))
    )
    (comp (ref "R197")
      (value "10Ω")
      (footprint "easyedapro:R0402")
      (description "电阻类型:厚膜电阻;阻值:10Ω;精度:±1%;功率:62.5mW;工作电压:50V;温度系数:±200ppm/℃;")
      (fields
        (field (name "Manufacturer Part") "0402WGF100JTCE")
        (field (name "Manufacturer") "UNI-ROYAL(厚声)")
      )
      (libsource (lib "easyedapro") (part "电阻"))
    )
    (comp (ref "R198")
      (value "10Ω")
      (footprint "easyedapro:R0402")
      (description "电阻类型:厚膜电阻;阻值:10Ω;精度:±1%;功率:62.5mW;工作电压:50V;温度系数:±200ppm/℃;")
      (fields
        (field (name "Manufacturer Part") "0402WGF100JTCE")
        (field (name "Manufacturer") "UNI-ROYAL(厚声)")
      )
      (libsource (lib "easyedapro") (part "电阻"))
    )
    (comp (ref "R199")
      (value "10Ω")
      (footprint "easyedapro:R0402")
      (description "电阻类型:厚膜电阻;阻值:10Ω;精度:±1%;功率:62.5mW;工作电压:50V;温度系数:±200ppm/℃;")
      (fields
        (field (name "Manufacturer Part") "0402WGF100JTCE")
        (field (name "Manufacturer") "UNI-ROYAL(厚声)")
      )
      (libsource (lib "easyedapro") (part "电阻"))
    )
    (comp (ref "R200")
      (value "10Ω")
      (footprint "easyedapro:R0402")
      (description "电阻类型:厚膜电阻;阻值:10Ω;精度:±1%;功率:62.5mW;工作电压:50V;温度系数:±200ppm/℃;")
      (fields
        (field (name "Manufacturer Part") "0402WGF100JTCE")
        (field (name "Manufacturer") "UNI-ROYAL(厚声)")
      )
      (libsource (lib "easyedapro") (part "电阻"))
    )
    (comp (ref "R201")
      (value "10Ω")
      (footprint "easyedapro:R0402")
      (description "电阻类型:厚膜电阻;阻值:10Ω;精度:±1%;功率:62.5mW;工作电压:50V;温度系数:±200ppm/℃;")
      (fields
        (field (name "Manufacturer Part") "0402WGF100JTCE")
        (field (name "Manufacturer") "UNI-ROYAL(厚声)")
      )
      (libsource (lib "easyedapro") (part "电阻"))
    )
    (comp (ref "R202")
      (value "10Ω")
      (footprint "easyedapro:R0402")
      (description "电阻类型:厚膜电阻;阻值:10Ω;精度:±1%;功率:62.5mW;工作电压:50V;温度系数:±200ppm/℃;")
      (fields
        (field (name "Manufacturer Part") "0402WGF100JTCE")
        (field (name "Manufacturer") "UNI-ROYAL(厚声)")
      )
      (libsource (lib "easyedapro") (part "电阻"))
    )
    (comp (ref "R206")
      (value "NCP15XH103F03RC")
      (footprint "easyedapro:R0402")
      (description "阻值:10kΩ;B值(25°C/50°C):3380K;电阻精度:±1%;功率:100mW;B值精度:±1%;最大稳态电流(25°C):310uA;")
      (fields (field (name "Manufacturer") "muRata(村田)"))
      (libsource (lib "easyedapro") (part "NCP15XH103F03RC"))
    )
    (comp (ref "R207")
      (value "3kΩ")
      (footprint "easyedapro:R0402")
      (fields
        (field (name "Manufacturer Part") "0402WGF3001TCE")
        (field (name "Manufacturer") "UNI-ROYAL(厚声)")
      )
      (libsource (lib "easyedapro") (part "电阻"))
    )
    (comp (ref "R239")
      (value "200kΩ")
      (footprint "easyedapro:R0402")
      (fields
        (field (name "Manufacturer Part") "0402WGF2003TCE")
        (field (name "Manufacturer") "UNI-ROYAL(厚声)")
      )
      (libsource (lib "easyedapro") (part "电阻"))
    )
    (comp (ref "R240")
      (value "200kΩ")
      (footprint "easyedapro:R0402")
      (fields
        (field (name "Manufacturer Part") "0402WGF2003TCE")
        (field (name "Manufacturer") "UNI-ROYAL(厚声)")
      )
      (libsource (lib "easyedapro") (part "电阻"))
    )
    (comp (ref "R241")
      (value "200kΩ")
      (footprint "easyedapro:R0402")
      (fields
        (field (name "Manufacturer Part") "0402WGF2003TCE")
        (field (name "Manufacturer") "UNI-ROYAL(厚声)")
      )
      (libsource (lib "easyedapro") (part "电阻"))
    )
    (comp (ref "U")
      (value "~")
      (footprint "easyedapro:PAD_35A")
      (description "焊盘")
      (libsource (lib "easyedapro") (part "PAD_35A"))
    )
    (comp (ref "U45")
      (value "IRS21867STRPBF-JSM")
      (footprint "easyedapro:SOIC-8_L4.9-W3.9-P1.27-LS6.0-BL")
      (description "驱动配置:半桥;负载类型:MOSFET;灌电流(IOL):4A;拉电流(IOH):4A;工作电压:10V~20V;")
      (fields (field (name "Manufacturer") "JSMSEMI(杰盛微)"))
      (libsource (lib "easyedapro") (part "IRS21867STR-JSM"))
    )
    (comp (ref "U46")
      (value "IRS21867STRPBF-JSM")
      (footprint "easyedapro:SOIC-8_L4.9-W3.9-P1.27-LS6.0-BL")
      (description "驱动配置:半桥;负载类型:MOSFET;灌电流(IOL):4A;拉电流(IOH):4A;工作电压:10V~20V;")
      (fields (field (name "Manufacturer") "JSMSEMI(杰盛微)"))
      (libsource (lib "easyedapro") (part "IRS21867STR-JSM"))
    )
    (comp (ref "U47")
      (value "IRS21867STRPBF-JSM")
      (footprint "easyedapro:SOIC-8_L4.9-W3.9-P1.27-LS6.0-BL")
      (description "驱动配置:半桥;负载类型:MOSFET;灌电流(IOL):4A;拉电流(IOH):4A;工作电压:10V~20V;")
      (fields (field (name "Manufacturer") "JSMSEMI(杰盛微)"))
      (libsource (lib "easyedapro") (part "IRS21867STR-JSM"))
    )
    (comp (ref "V")
      (value "~")
      (footprint "easyedapro:PAD_35A")
      (description "焊盘")
      (libsource (lib "easyedapro") (part "PAD_35A"))
    )
    (comp (ref "W")
      (value "~")
      (footprint "easyedapro:PAD_35A")
      (description "焊盘")
      (libsource (lib "easyedapro") (part "PAD_35A"))
    )
    (comp (ref "C231")
      (value "100pF")
      (footprint "easyedapro:C0402")
      (fields (field (name "Manufacturer Part") "0402CG101J500NT") (field (name "Manufacturer") "FH(风华)"))
      (libsource (lib "easyedapro") (part "CapAcitance"))
    )
    (comp (ref "GND")
      (value "~")
      (footprint "easyedapro:M3.5金属化螺丝孔")
      (libsource (lib "easyedapro") (part "监测孔"))
    )
    (comp (ref "OP3_OUT")
      (value "~")
      (footprint "easyedapro:M3.5金属化螺丝孔")
      (libsource (lib "easyedapro") (part "监测孔"))
    )
    (comp (ref "R211")
      (value "51kΩ")
      (footprint "easyedapro:R0402")
      (fields
        (field (name "Manufacturer Part") "0402WGF5102TCE")
        (field (name "Manufacturer") "UNI-ROYAL(厚声)")
      )
      (libsource (lib "easyedapro") (part "电阻"))
    )
    (comp (ref "R213")
      (value "3kΩ")
      (footprint "easyedapro:R0402")
      (fields (field (name "Manufacturer Part") "FRC0402F3001TS") (field (name "Manufacturer") "FOJAN(富捷)"))
      (libsource (lib "easyedapro") (part "电阻"))
    )
    (comp (ref "R214")
      (value "43kΩ")
      (footprint "easyedapro:R0402")
      (fields
        (field (name "Manufacturer Part") "0402WGF4302TCE")
        (field (name "Manufacturer") "UNI-ROYAL(厚声)")
      )
      (libsource (lib "easyedapro") (part "电阻"))
    )
    (comp (ref "R215")
      (value "51kΩ")
      (footprint "easyedapro:R0402")
      (fields
        (field (name "Manufacturer Part") "0402WGF5102TCE")
        (field (name "Manufacturer") "UNI-ROYAL(厚声)")
      )
      (libsource (lib "easyedapro") (part "电阻"))
    )
    (comp (ref "R216")
      (value "43kΩ")
      (footprint "easyedapro:R0402")
      (fields
        (field (name "Manufacturer Part") "0402WGF4302TCE")
        (field (name "Manufacturer") "UNI-ROYAL(厚声)")
      )
      (libsource (lib "easyedapro") (part "电阻"))
    )
    (comp (ref "R217")
      (value "3kΩ")
      (footprint "easyedapro:R0402")
      (fields (field (name "Manufacturer Part") "FRC0402F3001TS") (field (name "Manufacturer") "FOJAN(富捷)"))
      (libsource (lib "easyedapro") (part "电阻"))
    )
    (comp (ref "R218")
      (value "51kΩ")
      (footprint "easyedapro:R0402")
      (fields
        (field (name "Manufacturer Part") "0402WGF5102TCE")
        (field (name "Manufacturer") "UNI-ROYAL(厚声)")
      )
      (libsource (lib "easyedapro") (part "电阻"))
    )
    (comp (ref "R219")
      (value "43kΩ")
      (footprint "easyedapro:R0402")
      (fields
        (field (name "Manufacturer Part") "0402WGF4302TCE")
        (field (name "Manufacturer") "UNI-ROYAL(厚声)")
      )
      (libsource (lib "easyedapro") (part "电阻"))
    )
    (comp (ref "R220")
      (value "3kΩ")
      (footprint "easyedapro:R0402")
      (fields (field (name "Manufacturer Part") "FRC0402F3001TS") (field (name "Manufacturer") "FOJAN(富捷)"))
      (libsource (lib "easyedapro") (part "电阻"))
    )
    (comp (ref "R225")
      (value "1.2kΩ")
      (footprint "easyedapro:R0402")
      (description "电阻类型:薄膜电阻;阻值:1.2kΩ;精度:±0.1%;功率:63mW;工作电压:50V;温度系数:±25ppm/°C;")
      (fields (field (name "Manufacturer Part") "RT0402BRD071K2L") (field (name "Manufacturer") "YAGEO(国巨)"))
      (libsource (lib "easyedapro") (part "RT0402BRD071K2L"))
    )
    (comp (ref "R226")
      (value "1.2kΩ")
      (footprint "easyedapro:R0402")
      (description "电阻类型:薄膜电阻;阻值:1.2kΩ;精度:±0.1%;功率:63mW;工作电压:50V;温度系数:±25ppm/°C;")
      (fields (field (name "Manufacturer Part") "RT0402BRD071K2L") (field (name "Manufacturer") "YAGEO(国巨)"))
      (libsource (lib "easyedapro") (part "RT0402BRD071K2L"))
    )
    (comp (ref "R227")
      (value "1.2kΩ")
      (footprint "easyedapro:R0402")
      (description "电阻类型:薄膜电阻;阻值:1.2kΩ;精度:±0.1%;功率:63mW;工作电压:50V;温度系数:±25ppm/°C;")
      (fields (field (name "Manufacturer Part") "RT0402BRD071K2L") (field (name "Manufacturer") "YAGEO(国巨)"))
      (libsource (lib "easyedapro") (part "RT0402BRD071K2L"))
    )
    (comp (ref "R228")
      (value "1.2kΩ")
      (footprint "easyedapro:R0402")
      (description "电阻类型:薄膜电阻;阻值:1.2kΩ;精度:±0.1%;功率:63mW;工作电压:50V;温度系数:±25ppm/°C;")
      (fields (field (name "Manufacturer Part") "RT0402BRD071K2L") (field (name "Manufacturer") "YAGEO(国巨)"))
      (libsource (lib "easyedapro") (part "RT0402BRD071K2L"))
    )
    (comp (ref "R229")
      (value "66.5kΩ")
      (footprint "easyedapro:R0402")
      (description "电阻类型:薄膜电阻;阻值:66.5kΩ;精度:±0.1%;功率:62.5mW;工作电压:50V;温度系数:±25ppm/°C;")
      (fields (field (name "Manufacturer Part") "RT0402BRD0766K5L") (field (name "Manufacturer") "YAGEO(国巨)"))
      (libsource (lib "easyedapro") (part "RT0402BRD0766K5L"))
    )
    (comp (ref "R237")
      (value "133kΩ")
      (footprint "easyedapro:R0402")
      (description "电阻类型:薄膜电阻;阻值:133kΩ;精度:±0.1%;功率:63mW;温度系数:±25ppm/°C;")
      (fields (field (name "Manufacturer Part") "RT0402BRD07133KL") (field (name "Manufacturer") "YAGEO(国巨)"))
      (libsource (lib "easyedapro") (part "RT0402BRD07133KL"))
    )
    (comp (ref "R238")
      (value "133kΩ")
      (footprint "easyedapro:R0402")
      (description "电阻类型:薄膜电阻;阻值:133kΩ;精度:±0.1%;功率:63mW;温度系数:±25ppm/°C;")
      (fields (field (name "Manufacturer Part") "RT0402BRD07133KL") (field (name "Manufacturer") "YAGEO(国巨)"))
      (libsource (lib "easyedapro") (part "RT0402BRD07133KL"))
    )
  )
  (nets
    (net (code "1") (name "BOOT0") (class "Default")
      (node (ref "R188") (pin "1") (pinfunction "1_1") (pintype "input"))
      (node (ref "U34") (pin "31") (pinfunction "PF11/BOOT0_31") (pintype "unspecified"))
    )
    (net (code "2") (name "COM_NUTRAL") (class "Default")
      (node (ref "R211") (pin "1") (pinfunction "1_1") (pintype "input"))
      (node (ref "R215") (pin "1") (pinfunction "1_1") (pintype "input"))
      (node (ref "R218") (pin "1") (pinfunction "1_1") (pintype "input"))
      (node (ref "R224") (pin "1") (pinfunction "1_1") (pintype "input"))
    )
    (net (code "3") (name "EMF1") (class "Default")
      (node (ref "R211") (pin "2") (pinfunction "2_2") (pintype "input"))
      (node (ref "R213") (pin "1") (pinfunction "1_1") (pintype "input"))
      (node (ref "R214") (pin "1") (pinfunction "1_1") (pintype "input"))
      (node (ref "R221") (pin "1") (pinfunction "1_1") (pintype "input"))
    )
    (net (code "4") (name "EMF2") (class "Default")
      (node (ref "R215") (pin "2") (pinfunction "2_2") (pintype "input"))
      (node (ref "R216") (pin "1") (pinfunction "1_1") (pintype "input"))
      (node (ref "R217") (pin "1") (pinfunction "1_1") (pintype "input"))
      (node (ref "R222") (pin "1") (pinfunction "1_1") (pintype "input"))
    )
    (net (code "5") (name "EMF3") (class "Default")
      (node (ref "R218") (pin "2") (pinfunction "2_2") (pintype "input"))
      (node (ref "R219") (pin "1") (pinfunction "1_1") (pintype "input"))
      (node (ref "R220") (pin "1") (pinfunction "1_1") (pintype "input"))
      (node (ref "R223") (pin "1") (pinfunction "1_1") (pintype "input"))
    )
    (net (code "6") (name "EMF_NUTRAL") (class "Default")
      (node (ref "C230") (pin "2") (pinfunction "2_2") (pintype "input"))
      (node (ref "R224") (pin "2") (pinfunction "2_2") (pintype "input"))
      (node (ref "U34") (pin "13") (pinfunction "PA7_13") (pintype "unspecified"))
    )
    (net (code "7") (name "EMF_U") (class "Default")
      (node (ref "C227") (pin "2") (pinfunction "2_2") (pintype "input"))
      (node (ref "R221") (pin "2") (pinfunction "2_2") (pintype "input"))
      (node (ref "U34") (pin "10") (pinfunction "PA4_10") (pintype "unspecified"))
    )
    (net (code "8") (name "EMF_V") (class "Default")
      (node (ref "C228") (pin "2") (pinfunction "2_2") (pintype "input"))
      (node (ref "R222") (pin "2") (pinfunction "2_2") (pintype "input"))
      (node (ref "U34") (pin "11") (pinfunction "PA5_11") (pintype "unspecified"))
    )
    (net (code "9") (name "EMF_W") (class "Default")
      (node (ref "C229") (pin "2") (pinfunction "2_2") (pintype "input"))
      (node (ref "R223") (pin "2") (pinfunction "2_2") (pintype "input"))
      (node (ref "U34") (pin "12") (pinfunction "PA6_12") (pintype "unspecified"))
    )
    (net (code "10") (name "FB") (class "Default")
      (node (ref "R186") (pin "2") (pinfunction "2_2") (pintype "input"))
      (node (ref "R242") (pin "1") (pinfunction "1_1") (pintype "input"))
      (node (ref "U44") (pin "3") (pinfunction "FB_3") (pintype "unspecified"))
    )
    (net (code "11") (name "GND") (class "Default")
      (node (ref "ATLINK") (pin "3") (pinfunction "3_3") (pintype "unspecified"))
      (node (ref "C131") (pin "1") (pinfunction "1_1") (pintype "input"))
      (node (ref "C211") (pin "1") (pinfunction "1_1") (pintype "input"))
      (node (ref "C212") (pin "2") (pinfunction "2_2") (pintype "input"))
      (node (ref "C213") (pin "1") (pinfunction "1_1") (pintype "input"))
      (node (ref "C225") (pin "1") (pinfunction "1_1") (pintype "input"))
      (node (ref "C226") (pin "1") (pinfunction "1_1") (pintype "input"))
      (node (ref "C227") (pin "1") (pinfunction "1_1") (pintype "input"))
      (node (ref "C228") (pin "1") (pinfunction "1_1") (pintype "input"))
      (node (ref "C229") (pin "1") (pinfunction "1_1") (pintype "input"))
      (node (ref "C230") (pin "1") (pinfunction "1_1") (pintype "input"))
      (node (ref "C234") (pin "1") (pinfunction "1_1") (pintype "unspecified"))
      (node (ref "C235") (pin "1") (pinfunction "1_1") (pintype "unspecified"))
      (node (ref "C236") (pin "1") (pinfunction "1_1") (pintype "unspecified"))
      (node (ref "C253") (pin "1") (pinfunction "1_1") (pintype "unspecified"))
      (node (ref "DSHOT") (pin "2") (pinfunction "2_2") (pintype "input"))
      (node (ref "GND") (pin "1") (pinfunction "1_1") (pintype "input"))
      (node (ref "L12") (pin "4") (pinfunction "4_4") (pintype "unspecified"))
      (node (ref "LDO1") (pin "2") (pinfunction "VSS_2") (pintype "unspecified"))
      (node (ref "R188") (pin "2") (pinfunction "2_2") (pintype "input"))
      (node (ref "R213") (pin "2") (pinfunction "2_2") (pintype "input"))
      (node (ref "R217") (pin "2") (pinfunction "2_2") (pintype "input"))
      (node (ref "R220") (pin "2") (pinfunction "2_2") (pintype "input"))
      (node (ref "R238") (pin "1") (pinfunction "1_1") (pintype "unspecified"))
      (node (ref "U34") (pin "33") (pinfunction "EP_33") (pintype "unspecified"))
      (node (ref "UART") (pin "3") (pinfunction "3_3") (pintype "unspecified"))
      (node (ref "X3") (pin "2") (pinfunction "GND_2") (pintype "unspecified"))
      (node (ref "X3") (pin "4") (pinfunction "GND_4") (pintype "unspecified"))
    )
    (net (code "12") (name "GNDP") (class "Default")
      (node (ref "C221") (pin "1") (pinfunction "1_1") (pintype "unspecified"))
      (node (ref "C238") (pin "2") (pinfunction "2_2") (pintype "unspecified"))
      (node (ref "C239") (pin "2") (pinfunction "2_2") (pintype "unspecified"))
      (node (ref "C240") (pin "2") (pinfunction "2_2") (pintype "unspecified"))
      (node (ref "C241") (pin "2") (pinfunction "2_2") (pintype "input"))
      (node (ref "C249") (pin "1") (pinfunction "1_1") (pintype "unspecified"))
      (node (ref "C250") (pin "1") (pinfunction "1_1") (pintype "unspecified"))
      (node (ref "C252") (pin "1") (pinfunction "1_1") (pintype "unspecified"))
      (node (ref "C254") (pin "2") (pinfunction "2_2") (pintype "unspecified"))
      (node (ref "C255") (pin "2") (pinfunction "2_2") (pintype "unspecified"))
      (node (ref "C256") (pin "2") (pinfunction "2_2") (pintype "unspecified"))
      (node (ref "Q2") (pin "1") (pinfunction "S_1") (pintype "unspecified"))
      (node (ref "Q2") (pin "2") (pinfunction "S_2") (pintype "unspecified"))
      (node (ref "Q2") (pin "3") (pinfunction "S_3") (pintype "unspecified"))
      (node (ref "Q4") (pin "1") (pinfunction "S_1") (pintype "unspecified"))
      (node (ref "Q4") (pin "2") (pinfunction "S_2") (pintype "unspecified"))
      (node (ref "Q4") (pin "3") (pinfunction "S_3") (pintype "unspecified"))
      (node (ref "Q6") (pin "1") (pinfunction "S_1") (pintype "unspecified"))
      (node (ref "Q6") (pin "2") (pinfunction "S_2") (pintype "unspecified"))
      (node (ref "Q6") (pin "3") (pinfunction "S_3") (pintype "unspecified"))
      (node (ref "R203") (pin "1") (pinfunction "1_1") (pintype "unspecified"))
      (node (ref "R204") (pin "2") (pinfunction "2_2") (pintype "input"))
      (node (ref "R206") (pin "1") (pinfunction "1_1") (pintype "input"))
      (node (ref "U43") (pin "2") (pinfunction "GND_2") (pintype "unspecified"))
      (node (ref "U45") (pin "4") (pinfunction "COM_4") (pintype "unspecified"))
      (node (ref "U46") (pin "4") (pinfunction "COM_4") (pintype "unspecified"))
      (node (ref "U47") (pin "4") (pinfunction "COM_4") (pintype "unspecified"))
    )
    (net (code "13") (name "GND_IN") (class "Default")
      (node (ref "BUS_OUT") (pin "1") (pinfunction "1_1") (pintype "input"))
      (node (ref "C205") (pin "2") (pinfunction "2_2") (pintype "input"))
      (node (ref "C208") (pin "1") (pinfunction "1_1") (pintype "unspecified"))
      (node (ref "C210") (pin "1") (pinfunction "1_1") (pintype "unspecified"))
      (node (ref "C242") (pin "1") (pinfunction "1_1") (pintype "unspecified"))
      (node (ref "C245") (pin "1") (pinfunction "1_1") (pintype "unspecified"))
      (node (ref "C246") (pin "1") (pinfunction "1_1") (pintype "unspecified"))
      (node (ref "C247") (pin "1") (pinfunction "1_1") (pintype "unspecified"))
      (node (ref "D46") (pin "2") (pinfunction "A_2") (pintype "unspecified"))
      (node (ref "L12") (pin "1") (pinfunction "1_1") (pintype "unspecified"))
      (node (ref "R203") (pin "2") (pinfunction "2_2") (pintype "unspecified"))
      (node (ref "R205") (pin "2") (pinfunction "2_2") (pintype "input"))
      (node (ref "R231") (pin "2") (pinfunction "2_2") (pintype "input"))
      (node (ref "R242") (pin "2") (pinfunction "2_2") (pintype "input"))
      (node (ref "U41") (pin "2") (pinfunction "A_2") (pintype "unspecified"))
      (node (ref "U44") (pin "2") (pinfunction "GND_2") (pintype "unspecified"))
    )
    (net (code "14") (name "I_BUS_GND") (class "Default")
      (node (ref "C220") (pin "2") (pinfunction "2_2") (pintype "input"))
      (node (ref "R205") (pin "1") (pinfunction "1_1") (pintype "input"))
      (node (ref "R226") (pin "1") (pinfunction "1_1") (pintype "unspecified"))
    )
    (net (code "15") (name "I_BUS_SHUNT") (class "Default")
      (node (ref "C220") (pin "1") (pinfunction "1_1") (pintype "input"))
      (node (ref "R204") (pin "1") (pinfunction "1_1") (pintype "input"))
      (node (ref "R225") (pin "1") (pinfunction "1_1") (pintype "unspecified"))
    )
    (net (code "16") (name "LED_G") (class "Default")
      (node (ref "LED1") (pin "1") (pinfunction "R-_1") (pintype "unspecified"))
      (node (ref "U34") (pin "17") (pinfunction "PB10_17") (pintype "unspecified"))
    )
    (net (code "17") (name "LED_R") (class "Default")
      (node (ref "LED1") (pin "3") (pinfunction "UG-_3") (pintype "unspecified"))
      (node (ref "U34") (pin "7") (pinfunction "PA1_7") (pintype "unspecified"))
    )
    (net (code "18") (name "MOS_NTC") (class "Default")
      (node (ref "R206") (pin "2") (pinfunction "2_2") (pintype "input"))
      (node (ref "R207") (pin "1") (pinfunction "1_1") (pintype "input"))
      (node (ref "R209") (pin "1") (pinfunction "1_1") (pintype "input"))
    )
    (net (code "19") (name "MOS_TEMP") (class "Default")
      (node (ref "C226") (pin "2") (pinfunction "2_2") (pintype "input"))
      (node (ref "R209") (pin "2") (pinfunction "2_2") (pintype "input"))
      (node (ref "U34") (pin "5") (pinfunction "PF9_5") (pintype "unspecified"))
    )
    (net (code "20") (name "NRST") (class "Default")
      (node (ref "C211") (pin "2") (pinfunction "2_2") (pintype "input"))
      (node (ref "U34") (pin "4") (pinfunction "NRST/PF2_4") (pintype "unspecified"))
    )
    (net (code "21") (name "Net-(C231-Pad1)") (class "Default")
      (node (ref "C231") (pin "1") (pinfunction "1_1") (pintype "input"))
      (node (ref "R226") (pin "2") (pinfunction "2_2") (pintype "unspecified"))
      (node (ref "R228") (pin "1") (pinfunction "1_1") (pintype "unspecified"))
    )
    (net (code "22") (name "Net-(C231-Pad2)") (class "Default")
      (node (ref "C231") (pin "2") (pinfunction "2_2") (pintype "input"))
      (node (ref "R225") (pin "2") (pinfunction "2_2") (pintype "unspecified"))
      (node (ref "R227") (pin "1") (pinfunction "1_1") (pintype "unspecified"))
    )
    (net (code "23") (name "Net-(D37-K)") (class "Default")
      (node (ref "C215") (pin "2") (pinfunction "2_2") (pintype "unspecified"))
      (node (ref "D37") (pin "1") (pinfunction "K_1") (pintype "unspecified"))
      (node (ref "U45") (pin "8") (pinfunction "VB_8") (pintype "unspecified"))
    )
    (net (code "24") (name "Net-(D38-K)") (class "Default")
      (node (ref "C217") (pin "2") (pinfunction "2_2") (pintype "unspecified"))
      (node (ref "D38") (pin "1") (pinfunction "K_1") (pintype "unspecified"))
      (node (ref "U46") (pin "8") (pinfunction "VB_8") (pintype "unspecified"))
    )
    (net (code "25") (name "Net-(D39-K)") (class "Default")
      (node (ref "C219") (pin "2") (pinfunction "2_2") (pintype "unspecified"))
      (node (ref "D39") (pin "1") (pinfunction "K_1") (pintype "unspecified"))
      (node (ref "U47") (pin "8") (pinfunction "VB_8") (pintype "unspecified"))
    )
    (net (code "26") (name "Net-(D40-A)") (class "Default")
      (node (ref "D40") (pin "2") (pinfunction "A_2") (pintype "unspecified"))
      (node (ref "Q1") (pin "4") (pinfunction "G_4") (pintype "unspecified"))
      (node (ref "R191") (pin "2") (pinfunction "2_2") (pintype "input"))
      (node (ref "R239") (pin "2") (pinfunction "2_2") (pintype "input"))
    )
    (net (code "27") (name "Net-(D40-K)") (class "Default")
      (node (ref "D40") (pin "1") (pinfunction "K_1") (pintype "unspecified"))
      (node (ref "R191") (pin "1") (pinfunction "1_1") (pintype "input"))
      (node (ref "U45") (pin "7") (pinfunction "HO_7") (pintype "unspecified"))
    )
    (net (code "28") (name "Net-(D41-A)") (class "Default")
      (node (ref "D41") (pin "2") (pinfunction "A_2") (pintype "unspecified"))
      (node (ref "Q3") (pin "4") (pinfunction "G_4") (pintype "unspecified"))
      (node (ref "R193") (pin "2") (pinfunction "2_2") (pintype "input"))
      (node (ref "R240") (pin "2") (pinfunction "2_2") (pintype "input"))
    )
    (net (code "29") (name "Net-(D41-K)") (class "Default")
      (node (ref "D41") (pin "1") (pinfunction "K_1") (pintype "unspecified"))
      (node (ref "R193") (pin "1") (pinfunction "1_1") (pintype "input"))
      (node (ref "U46") (pin "7") (pinfunction "HO_7") (pintype "unspecified"))
    )
    (net (code "30") (name "Net-(D42-A)") (class "Default")
      (node (ref "D42") (pin "2") (pinfunction "A_2") (pintype "unspecified"))
      (node (ref "Q5") (pin "4") (pinfunction "G_4") (pintype "unspecified"))
      (node (ref "R195") (pin "2") (pinfunction "2_2") (pintype "input"))
      (node (ref "R241") (pin "2") (pinfunction "2_2") (pintype "input"))
    )
    (net (code "31") (name "Net-(D42-K)") (class "Default")
      (node (ref "D42") (pin "1") (pinfunction "K_1") (pintype "unspecified"))
      (node (ref "R195") (pin "1") (pinfunction "1_1") (pintype "input"))
      (node (ref "U47") (pin "7") (pinfunction "HO_7") (pintype "unspecified"))
    )
    (net (code "32") (name "Net-(D43-A)") (class "Default")
      (node (ref "D43") (pin "2") (pinfunction "A_2") (pintype "unspecified"))
      (node (ref "Q2") (pin "4") (pinfunction "G_4") (pintype "unspecified"))
      (node (ref "R192") (pin "2") (pinfunction "2_2") (pintype "input"))
    )
    (net (code "33") (name "Net-(D43-K)") (class "Default")
      (node (ref "D43") (pin "1") (pinfunction "K_1") (pintype "unspecified"))
      (node (ref "R192") (pin "1") (pinfunction "1_1") (pintype "input"))
      (node (ref "U45") (pin "5") (pinfunction "LO_5") (pintype "unspecified"))
    )
    (net (code "34") (name "Net-(D44-A)") (class "Default")
      (node (ref "D44") (pin "2") (pinfunction "A_2") (pintype "unspecified"))
      (node (ref "Q4") (pin "4") (pinfunction "G_4") (pintype "unspecified"))
      (node (ref "R194") (pin "2") (pinfunction "2_2") (pintype "input"))
    )
    (net (code "35") (name "Net-(D44-K)") (class "Default")
      (node (ref "D44") (pin "1") (pinfunction "K_1") (pintype "unspecified"))
      (node (ref "R194") (pin "1") (pinfunction "1_1") (pintype "input"))
      (node (ref "U46") (pin "5") (pinfunction "LO_5") (pintype "unspecified"))
    )
    (net (code "36") (name "Net-(D45-A)") (class "Default")
      (node (ref "D45") (pin "2") (pinfunction "A_2") (pintype "unspecified"))
      (node (ref "Q6") (pin "4") (pinfunction "G_4") (pintype "unspecified"))
      (node (ref "R196") (pin "2") (pinfunction "2_2") (pintype "input"))
    )
    (net (code "37") (name "Net-(D45-K)") (class "Default")
      (node (ref "D45") (pin "1") (pinfunction "K_1") (pintype "unspecified"))
      (node (ref "R196") (pin "1") (pinfunction "1_1") (pintype "input"))
      (node (ref "U47") (pin "5") (pinfunction "LO_5") (pintype "unspecified"))
    )
    (net (code "38") (name "Net-(D46-K)") (class "Default")
      (node (ref "C232") (pin "2") (pinfunction "2_2") (pintype "unspecified"))
      (node (ref "D46") (pin "1") (pinfunction "K_1") (pintype "unspecified"))
      (node (ref "L16") (pin "2") (pinfunction "2_2") (pintype "unspecified"))
      (node (ref "U44") (pin "6") (pinfunction "SW_6") (pintype "unspecified"))
    )
    (net (code "39") (name "Net-(LDO1-CE)") (class "Default")
      (node (ref "C235") (pin "2") (pinfunction "2_2") (pintype "unspecified"))
      (node (ref "LDO1") (pin "3") (pinfunction "CE_3") (pintype "unspecified"))
      (node (ref "R243") (pin "1") (pinfunction "1_1") (pintype "input"))
    )
    (net (code "40") (name "Net-(LDO1-VIN)") (class "Default")
      (node (ref "C234") (pin "2") (pinfunction "2_2") (pintype "unspecified"))
      (node (ref "L12") (pin "3") (pinfunction "3_3") (pintype "unspecified"))
      (node (ref "LDO1") (pin "1") (pinfunction "VIN_1") (pintype "unspecified"))
      (node (ref "R243") (pin "2") (pinfunction "2_2") (pintype "input"))
    )
    (net (code "41") (name "Net-(LED1-+R)") (class "Default")
      (node (ref "LED1") (pin "2") (pinfunction "+R_2") (pintype "unspecified"))
      (node (ref "R190") (pin "2") (pinfunction "2_2") (pintype "input"))
    )
    (net (code "42") (name "Net-(LED1-+UG)") (class "Default")
      (node (ref "LED1") (pin "4") (pinfunction "+UG_4") (pintype "unspecified"))
      (node (ref "R189") (pin "2") (pinfunction "2_2") (pintype "input"))
    )
    (net (code "43") (name "Net-(U34-PA11)") (class "Default")
      (node (ref "PA11") (pin "1") (pinfunction "1_1") (pintype "input"))
      (node (ref "U34") (pin "21") (pinfunction "PA11_21") (pintype "unspecified"))
    )
    (net (code "44") (name "Net-(U34-PA15)") (class "Default")
      (node (ref "PA15") (pin "1") (pinfunction "1_1") (pintype "input"))
      (node (ref "U34") (pin "25") (pinfunction "PA15_25") (pintype "unspecified"))
    )
    (net (code "45") (name "Net-(U34-PB3)") (class "Default")
      (node (ref "PB3") (pin "1") (pinfunction "1_1") (pintype "input"))
      (node (ref "U34") (pin "26") (pinfunction "PB3_26") (pintype "unspecified"))
    )
    (net (code "46") (name "Net-(U34-PB4)") (class "Default")
      (node (ref "PB4") (pin "1") (pinfunction "1_1") (pintype "input"))
      (node (ref "U34") (pin "27") (pinfunction "PB4_27") (pintype "unspecified"))
    )
    (net (code "47") (name "Net-(U34-PB5)") (class "Default")
      (node (ref "PB5") (pin "1") (pinfunction "1_1") (pintype "input"))
      (node (ref "U34") (pin "28") (pinfunction "PB5_28") (pintype "unspecified"))
    )
    (net (code "48") (name "Net-(U44-BST)") (class "Default")
      (node (ref "C232") (pin "1") (pinfunction "1_1") (pintype "unspecified"))
      (node (ref "U44") (pin "1") (pinfunction "BST_1") (pintype "unspecified"))
    )
    (net (code "49") (name "Net-(U44-EN)") (class "Default")
      (node (ref "C242") (pin "2") (pinfunction "2_2") (pintype "unspecified"))
      (node (ref "U44") (pin "4") (pinfunction "EN_4") (pintype "unspecified"))
    )
    (net (code "50") (name "Net-(U45-HIN)") (class "Default")
      (node (ref "R197") (pin "2") (pinfunction "2_2") (pintype "input"))
      (node (ref "U45") (pin "2") (pinfunction "HIN_2") (pintype "unspecified"))
    )
    (net (code "51") (name "Net-(U45-LIN)") (class "Default")
      (node (ref "R198") (pin "2") (pinfunction "2_2") (pintype "input"))
      (node (ref "U45") (pin "3") (pinfunction "LIN_3") (pintype "unspecified"))
    )
    (net (code "52") (name "Net-(U46-HIN)") (class "Default")
      (node (ref "R199") (pin "2") (pinfunction "2_2") (pintype "input"))
      (node (ref "U46") (pin "2") (pinfunction "HIN_2") (pintype "unspecified"))
    )
    (net (code "53") (name "Net-(U46-LIN)") (class "Default")
      (node (ref "R200") (pin "2") (pinfunction "2_2") (pintype "input"))
      (node (ref "U46") (pin "3") (pinfunction "LIN_3") (pintype "unspecified"))
    )
    (net (code "54") (name "Net-(U47-HIN)") (class "Default")
      (node (ref "R201") (pin "2") (pinfunction "2_2") (pintype "input"))
      (node (ref "U47") (pin "2") (pinfunction "HIN_2") (pintype "unspecified"))
    )
    (net (code "55") (name "Net-(U47-LIN)") (class "Default")
      (node (ref "R202") (pin "2") (pinfunction "2_2") (pintype "input"))
      (node (ref "U47") (pin "3") (pinfunction "LIN_3") (pintype "unspecified"))
    )
    (net (code "56") (name "OP3_INM_BUS") (class "Default")
      (node (ref "R228") (pin "2") (pinfunction "2_2") (pintype "unspecified"))
      (node (ref "R229") (pin "1") (pinfunction "1_1") (pintype "unspecified"))
      (node (ref "U34") (pin "16") (pinfunction "PB2_16") (pintype "unspecified"))
    )
    (net (code "57") (name "OP3_INP_BUS") (class "Default")
      (node (ref "R227") (pin "2") (pinfunction "2_2") (pintype "unspecified"))
      (node (ref "R237") (pin "2") (pinfunction "2_2") (pintype "unspecified"))
      (node (ref "R238") (pin "2") (pinfunction "2_2") (pintype "unspecified"))
      (node (ref "U34") (pin "14") (pinfunction "PB0_14") (pintype "unspecified"))
    )
    (net (code "58") (name "OP3_OUT_BUS") (class "Default")
      (node (ref "OP3_OUT") (pin "1") (pinfunction "1_1") (pintype "input"))
      (node (ref "R229") (pin "2") (pinfunction "2_2") (pintype "unspecified"))
      (node (ref "U34") (pin "15") (pinfunction "PB1_15") (pintype "unspecified"))
    )
    (net (code "59") (name "OSC_IN") (class "Default")
      (node (ref "C212") (pin "1") (pinfunction "1_1") (pintype "input"))
      (node (ref "U34") (pin "2") (pinfunction "PF0_2") (pintype "unspecified"))
      (node (ref "X3") (pin "1") (pinfunction "OSC1_1") (pintype "unspecified"))
    )
    (net (code "60") (name "OSC_OUT") (class "Default")
      (node (ref "C213") (pin "2") (pinfunction "2_2") (pintype "input"))
      (node (ref "U34") (pin "3") (pinfunction "PF1_3") (pintype "unspecified"))
      (node (ref "X3") (pin "3") (pinfunction "OSC2_3") (pintype "unspecified"))
    )
    (net (code "61") (name "OUT1") (class "Default")
      (node (ref "C215") (pin "1") (pinfunction "1_1") (pintype "unspecified"))
      (node (ref "Q1") (pin "1") (pinfunction "S_1") (pintype "unspecified"))
      (node (ref "Q1") (pin "2") (pinfunction "S_2") (pintype "unspecified"))
      (node (ref "Q1") (pin "3") (pinfunction "S_3") (pintype "unspecified"))
      (node (ref "Q2") (pin "5") (pinfunction "D_5") (pintype "unspecified"))
      (node (ref "R214") (pin "2") (pinfunction "2_2") (pintype "input"))
      (node (ref "R239") (pin "1") (pinfunction "1_1") (pintype "input"))
      (node (ref "U") (pin "1") (pinfunction "1_1") (pintype "input"))
      (node (ref "U45") (pin "6") (pinfunction "VS_6") (pintype "unspecified"))
    )
    (net (code "62") (name "OUT2") (class "Default")
      (node (ref "C217") (pin "1") (pinfunction "1_1") (pintype "unspecified"))
      (node (ref "Q3") (pin "1") (pinfunction "S_1") (pintype "unspecified"))
      (node (ref "Q3") (pin "2") (pinfunction "S_2") (pintype "unspecified"))
      (node (ref "Q3") (pin "3") (pinfunction "S_3") (pintype "unspecified"))
      (node (ref "Q4") (pin "5") (pinfunction "D_5") (pintype "unspecified"))
      (node (ref "R216") (pin "2") (pinfunction "2_2") (pintype "input"))
      (node (ref "R240") (pin "1") (pinfunction "1_1") (pintype "input"))
      (node (ref "U46") (pin "6") (pinfunction "VS_6") (pintype "unspecified"))
      (node (ref "V") (pin "1") (pinfunction "1_1") (pintype "input"))
    )
    (net (code "63") (name "OUT3") (class "Default")
      (node (ref "C219") (pin "1") (pinfunction "1_1") (pintype "unspecified"))
      (node (ref "Q5") (pin "1") (pinfunction "S_1") (pintype "unspecified"))
      (node (ref "Q5") (pin "2") (pinfunction "S_2") (pintype "unspecified"))
      (node (ref "Q5") (pin "3") (pinfunction "S_3") (pintype "unspecified"))
      (node (ref "Q6") (pin "5") (pinfunction "D_5") (pintype "unspecified"))
      (node (ref "R219") (pin "2") (pinfunction "2_2") (pintype "input"))
      (node (ref "R241") (pin "1") (pinfunction "1_1") (pintype "input"))
      (node (ref "U47") (pin "6") (pinfunction "VS_6") (pintype "unspecified"))
      (node (ref "W") (pin "1") (pinfunction "1_1") (pintype "input"))
    )
    (net (code "64") (name "PWM_IN_DSHOT") (class "Default")
      (node (ref "DSHOT") (pin "1") (pinfunction "1_1") (pintype "input"))
      (node (ref "U34") (pin "32") (pinfunction "PB8_32") (pintype "unspecified"))
    )
    (net (code "65") (name "SWCLK") (class "Default")
      (node (ref "ATLINK") (pin "2") (pinfunction "2_2") (pintype "unspecified"))
      (node (ref "U34") (pin "24") (pinfunction "PA14_24") (pintype "unspecified"))
    )
    (net (code "66") (name "SWDIO") (class "Default")
      (node (ref "ATLINK") (pin "1") (pinfunction "1_1") (pintype "unspecified"))
      (node (ref "U34") (pin "23") (pinfunction "PA13_23") (pintype "unspecified"))
    )
    (net (code "67") (name "TIM1_CH1") (class "Default")
      (node (ref "R197") (pin "1") (pinfunction "1_1") (pintype "input"))
      (node (ref "U34") (pin "18") (pinfunction "PA8_18") (pintype "unspecified"))
    )
    (net (code "68") (name "TIM1_CH1N") (class "Default")
      (node (ref "R198") (pin "1") (pinfunction "1_1") (pintype "input"))
      (node (ref "U34") (pin "30") (pinfunction "PB7_30") (pintype "unspecified"))
    )
    (net (code "69") (name "TIM1_CH2") (class "Default")
      (node (ref "R199") (pin "1") (pinfunction "1_1") (pintype "input"))
      (node (ref "U34") (pin "19") (pinfunction "PA9_19") (pintype "unspecified"))
    )
    (net (code "70") (name "TIM1_CH2N") (class "Default")
      (node (ref "R200") (pin "1") (pinfunction "1_1") (pintype "input"))
      (node (ref "U34") (pin "22") (pinfunction "PA12_22") (pintype "unspecified"))
    )
    (net (code "71") (name "TIM1_CH3") (class "Default")
      (node (ref "R201") (pin "1") (pinfunction "1_1") (pintype "input"))
      (node (ref "U34") (pin "20") (pinfunction "PA10_20") (pintype "unspecified"))
    )
    (net (code "72") (name "TIM1_CH3N") (class "Default")
      (node (ref "R202") (pin "1") (pinfunction "1_1") (pintype "input"))
      (node (ref "U34") (pin "29") (pinfunction "PB6_29") (pintype "unspecified"))
    )
    (net (code "73") (name "UART_RX") (class "Default")
      (node (ref "U34") (pin "9") (pinfunction "PA3_9") (pintype "unspecified"))
      (node (ref "UART") (pin "2") (pinfunction "2_2") (pintype "unspecified"))
    )
    (net (code "74") (name "UART_TX") (class "Default")
      (node (ref "U34") (pin "8") (pinfunction "PA2_8") (pintype "unspecified"))
      (node (ref "UART") (pin "1") (pinfunction "1_1") (pintype "unspecified"))
    )
    (net (code "75") (name "VBOOST") (class "Default")
      (node (ref "C254") (pin "1") (pinfunction "1_1") (pintype "unspecified"))
      (node (ref "C255") (pin "1") (pinfunction "1_1") (pintype "unspecified"))
      (node (ref "C256") (pin "1") (pinfunction "1_1") (pintype "unspecified"))
      (node (ref "D37") (pin "2") (pinfunction "A_2") (pintype "unspecified"))
      (node (ref "D38") (pin "2") (pinfunction "A_2") (pintype "unspecified"))
      (node (ref "D39") (pin "2") (pinfunction "A_2") (pintype "unspecified"))
      (node (ref "L14") (pin "2") (pinfunction "2_2") (pintype "unspecified"))
      (node (ref "L15") (pin "2") (pinfunction "2_2") (pintype "unspecified"))
      (node (ref "U45") (pin "1") (pinfunction "VCC_1") (pintype "unspecified"))
      (node (ref "U46") (pin "1") (pinfunction "VCC_1") (pintype "unspecified"))
      (node (ref "U47") (pin "1") (pinfunction "VCC_1") (pintype "unspecified"))
    )
    (net (code "76") (name "VBUS") (class "Default")
      (node (ref "BUS_IN") (pin "1") (pinfunction "1_1") (pintype "input"))
      (node (ref "C205") (pin "1") (pinfunction "1_1") (pintype "input"))
      (node (ref "C208") (pin "2") (pinfunction "2_2") (pintype "unspecified"))
      (node (ref "C221") (pin "2") (pinfunction "2_2") (pintype "unspecified"))
      (node (ref "C238") (pin "1") (pinfunction "1_1") (pintype "unspecified"))
      (node (ref "C239") (pin "1") (pinfunction "1_1") (pintype "unspecified"))
      (node (ref "C240") (pin "1") (pinfunction "1_1") (pintype "unspecified"))
      (node (ref "C245") (pin "2") (pinfunction "2_2") (pintype "unspecified"))
      (node (ref "C246") (pin "2") (pinfunction "2_2") (pintype "unspecified"))
      (node (ref "C247") (pin "2") (pinfunction "2_2") (pintype "unspecified"))
      (node (ref "C249") (pin "2") (pinfunction "2_2") (pintype "unspecified"))
      (node (ref "C250") (pin "2") (pinfunction "2_2") (pintype "unspecified"))
      (node (ref "C252") (pin "2") (pinfunction "2_2") (pintype "unspecified"))
      (node (ref "L15") (pin "1") (pinfunction "1_1") (pintype "unspecified"))
      (node (ref "Q1") (pin "5") (pinfunction "D_5") (pintype "unspecified"))
      (node (ref "Q3") (pin "5") (pinfunction "D_5") (pintype "unspecified"))
      (node (ref "Q5") (pin "5") (pinfunction "D_5") (pintype "unspecified"))
      (node (ref "R230") (pin "1") (pinfunction "1_1") (pintype "input"))
      (node (ref "U41") (pin "1") (pinfunction "C_1") (pintype "unspecified"))
      (node (ref "U43") (pin "3") (pinfunction "Vin_3") (pintype "unspecified"))
      (node (ref "U44") (pin "5") (pinfunction "VIN_5") (pintype "unspecified"))
    )
    (net (code "77") (name "VBUS_REF") (class "Default")
      (node (ref "R208") (pin "1") (pinfunction "1_1") (pintype "input"))
      (node (ref "R230") (pin "2") (pinfunction "2_2") (pintype "input"))
      (node (ref "R231") (pin "1") (pinfunction "1_1") (pintype "input"))
    )
    (net (code "78") (name "VCC_3V3") (class "Default")
      (node (ref "C236") (pin "2") (pinfunction "2_2") (pintype "unspecified"))
      (node (ref "L13") (pin "1") (pinfunction "1_1") (pintype "unspecified"))
      (node (ref "LDO1") (pin "5") (pinfunction "VOUT_5") (pintype "unspecified"))
    )
    (net (code "79") (name "VCC_5V") (class "Default")
      (node (ref "C210") (pin "2") (pinfunction "2_2") (pintype "unspecified"))
      (node (ref "L12") (pin "2") (pinfunction "2_2") (pintype "unspecified"))
      (node (ref "L16") (pin "1") (pinfunction "1_1") (pintype "unspecified"))
      (node (ref "R186") (pin "1") (pinfunction "1_1") (pintype "input"))
    )
    (net (code "80") (name "VCC_12V") (class "Default")
      (node (ref "C241") (pin "1") (pinfunction "1_1") (pintype "input"))
      (node (ref "L14") (pin "1") (pinfunction "1_1") (pintype "unspecified"))
      (node (ref "U43") (pin "1") (pinfunction "Vout_1") (pintype "unspecified"))
    )
    (net (code "81") (name "VDD_3V3") (class "Default")
      (node (ref "C131") (pin "2") (pinfunction "2_2") (pintype "input"))
      (node (ref "C253") (pin "2") (pinfunction "2_2") (pintype "unspecified"))
      (node (ref "L13") (pin "2") (pinfunction "2_2") (pintype "unspecified"))
      (node (ref "R189") (pin "1") (pinfunction "1_1") (pintype "input"))
      (node (ref "R190") (pin "1") (pinfunction "1_1") (pintype "input"))
      (node (ref "R207") (pin "2") (pinfunction "2_2") (pintype "input"))
      (node (ref "R237") (pin "1") (pinfunction "1_1") (pintype "unspecified"))
      (node (ref "U34") (pin "1") (pinfunction "VDD/VDDA_1") (pintype "unspecified"))
    )
    (net (code "82") (name "V_BUS_FB") (class "Default")
      (node (ref "C225") (pin "2") (pinfunction "2_2") (pintype "input"))
      (node (ref "R208") (pin "2") (pinfunction "2_2") (pintype "input"))
      (node (ref "U34") (pin "6") (pinfunction "PA0_6") (pintype "unspecified"))
    )
    (net (code "83") (name "unconnected-(LDO1-NC-Pad4)") (class "Default")
      (node (ref "LDO1") (pin "4") (pinfunction "NC_4") (pintype "unspecified+no_connect"))
    )
  )
)
